# KickerBoard-new.net
KiCad netlist of a schematic drawn in EAGLE
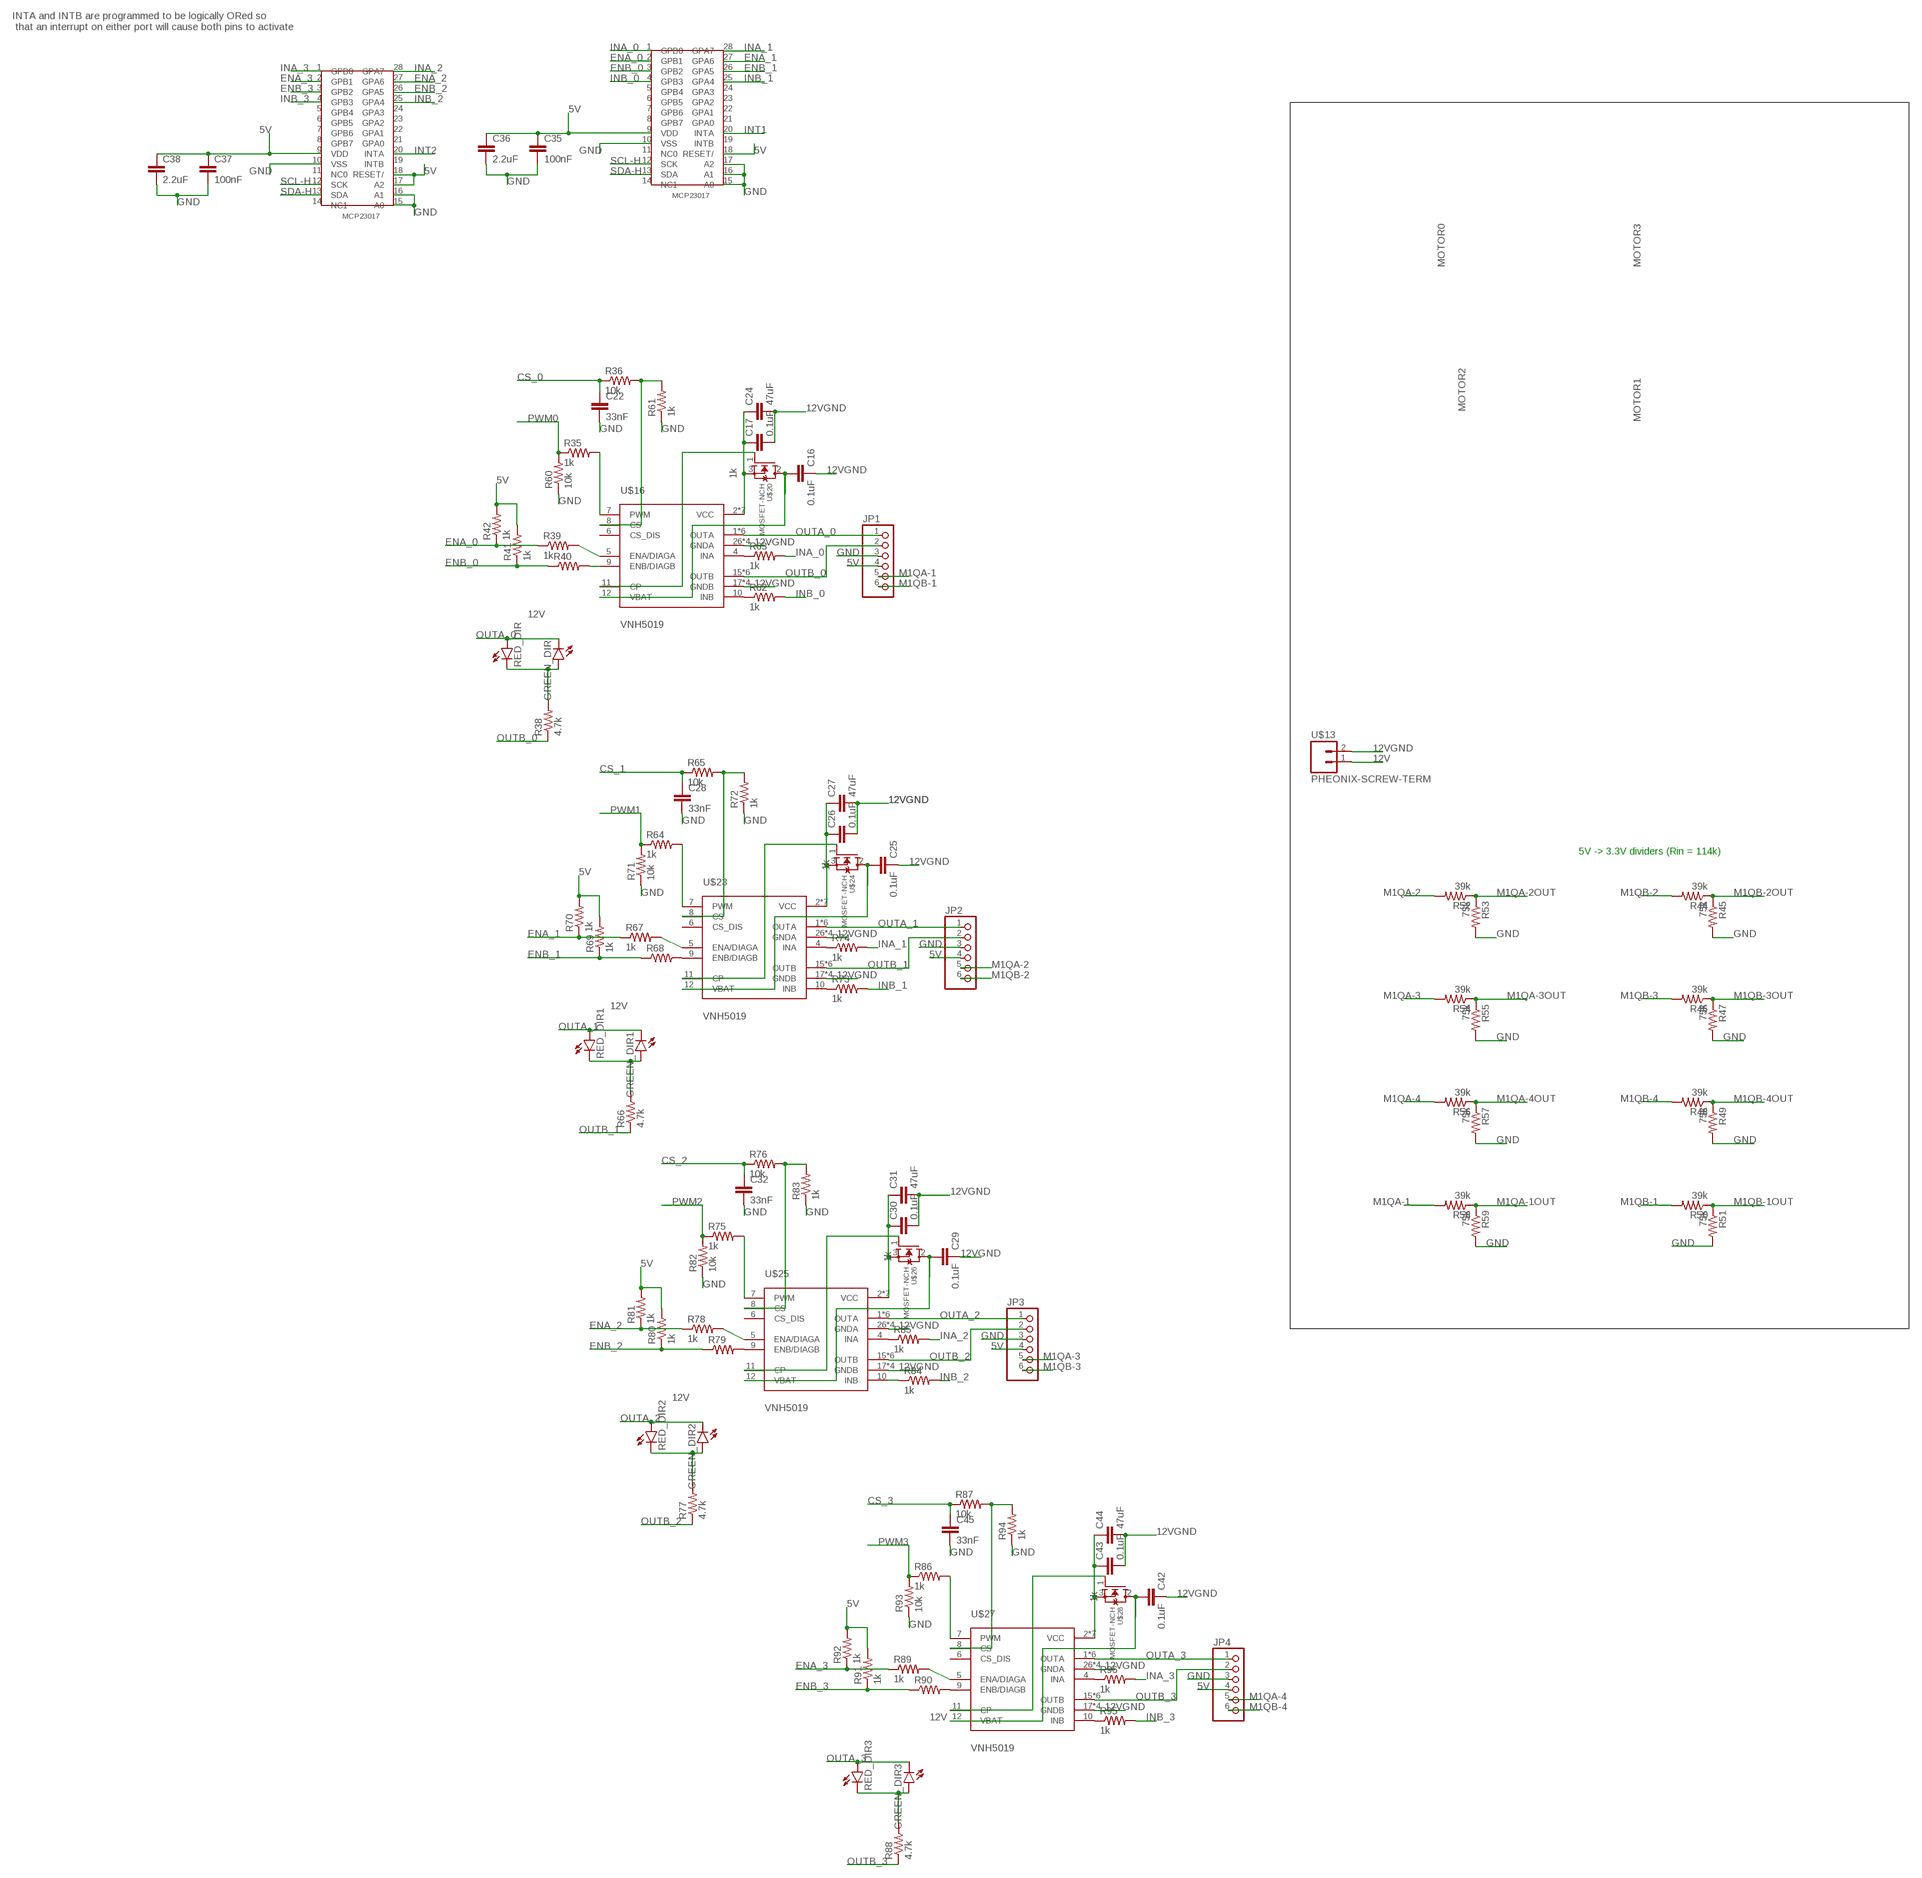
[diagram p0: schematic, sheet 1, part 1 of 3]
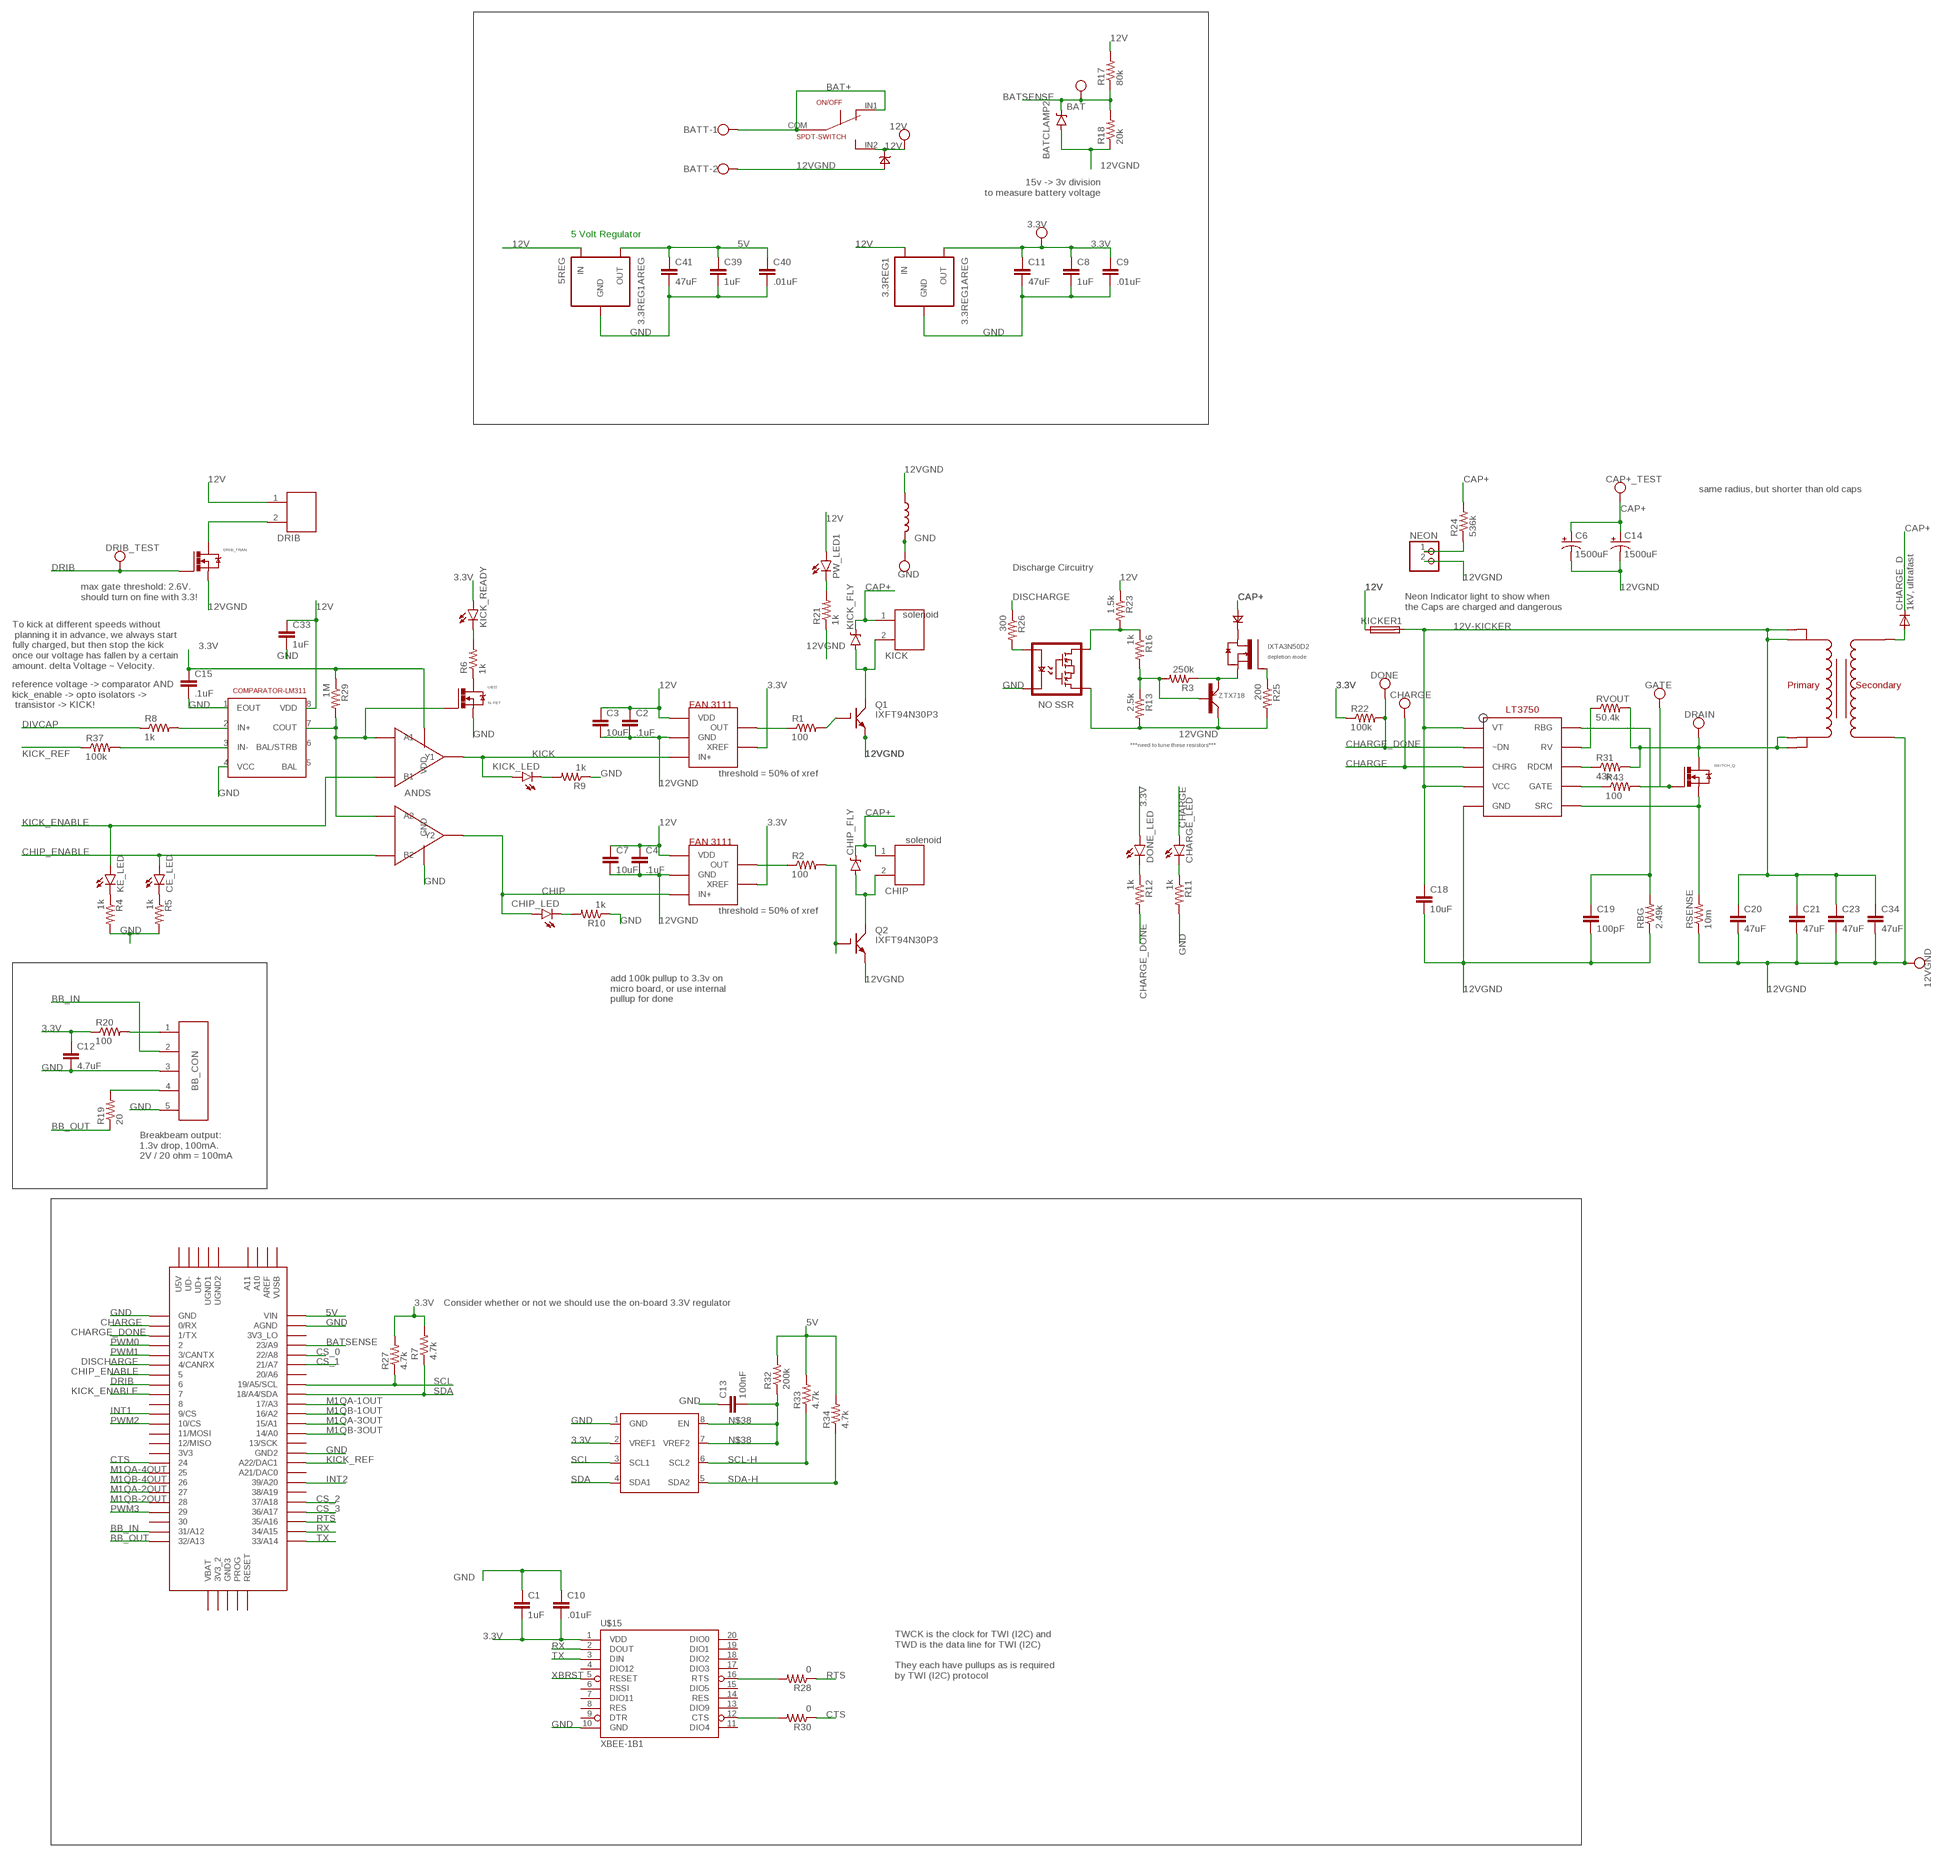
[diagram p1: schematic, sheet 1, part 2 of 3]
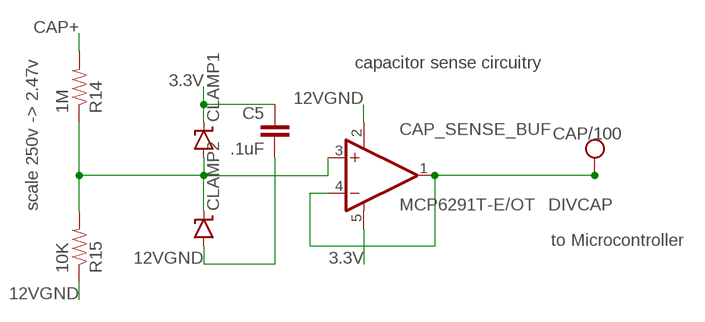
[diagram p2: schematic, sheet 1, part 3 of 3]

(export (version "E")
  (design (tool "Eeschema 10.0.6"))
  (components
    (comp (ref "3.3REG1")
      (value "3.3REG1AREG")
      (footprint "eagle-import:DPAK")
      (libsource (lib "eagle-import") (part "3.3REG1AREG"))
    )
    (comp (ref "3.3V")
      (value "TEST_PT")
      (footprint "eagle-import:TESTING_PT")
      (libsource (lib "eagle-import") (part "TEST_PT"))
    )
    (comp (ref "5REG")
      (value "3.3REG1AREG")
      (footprint "eagle-import:DPAK")
      (libsource (lib "eagle-import") (part "3.3REG1AREG"))
    )
    (comp (ref "12V")
      (value "TEST_PT")
      (footprint "eagle-import:TESTING_PT")
      (libsource (lib "eagle-import") (part "TEST_PT"))
    )
    (comp (ref "12VGND")
      (value "TEST_PT")
      (footprint "eagle-import:TESTING_PT")
      (libsource (lib "eagle-import") (part "TEST_PT"))
    )
    (comp (ref "ANDS")
      (value "AND-DUAL")
      (footprint "eagle-import:TSSOP8")
      (libsource (lib "eagle-import") (part "AND-DUAL"))
    )
    (comp (ref "BAT")
      (value "TEST_PT")
      (footprint "eagle-import:TESTING_PT")
      (libsource (lib "eagle-import") (part "TEST_PT"))
    )
    (comp (ref "BATCLAMP2")
      (value "DIODE-ZENERDO214AC")
      (footprint "eagle-import:DO214AC")
      (libsource (lib "eagle-import") (part "DIODE-ZENERDO214AC"))
    )
    (comp (ref "BATT")
      (value "W237-102")
      (footprint "eagle-import:W237-102")
      (fields (field (name "MPN") "237-102"))
      (libsource (lib "eagle-import") (part "W237-102"))
    )
    (comp (ref "BB_CON")
      (value "JST-5")
      (footprint "eagle-import:JST-5-2MM")
      (libsource (lib "eagle-import") (part "JST-5"))
    )
    (comp (ref "C1")
      (value "1uF")
      (footprint "eagle-import:1206")
      (libsource (lib "eagle-import") (part "CAP1206"))
    )
    (comp (ref "C2")
      (value ".1uF")
      (footprint "eagle-import:1206")
      (libsource (lib "eagle-import") (part "CAP1206"))
    )
    (comp (ref "C3")
      (value "10uF")
      (footprint "eagle-import:1206")
      (libsource (lib "eagle-import") (part "CAP1206"))
    )
    (comp (ref "C4")
      (value ".1uF")
      (footprint "eagle-import:1206")
      (libsource (lib "eagle-import") (part "CAP1206"))
    )
    (comp (ref "C5")
      (value ".1uF")
      (footprint "eagle-import:0805")
      (libsource (lib "eagle-import") (part "CAP0805"))
    )
    (comp (ref "C6")
      (value "1500uF")
      (footprint "eagle-import:EB35D")
      (libsource (lib "eagle-import") (part "CPOL-USE10-35"))
    )
    (comp (ref "C7")
      (value "10uF")
      (footprint "eagle-import:1206")
      (libsource (lib "eagle-import") (part "CAP1206"))
    )
    (comp (ref "C8")
      (value "1uF")
      (footprint "eagle-import:0805")
      (libsource (lib "eagle-import") (part "CAP0805"))
    )
    (comp (ref "C9")
      (value ".01uF")
      (footprint "eagle-import:0805")
      (libsource (lib "eagle-import") (part "CAP0805"))
    )
    (comp (ref "C10")
      (value ".01uF")
      (footprint "eagle-import:1206")
      (libsource (lib "eagle-import") (part "CAP1206"))
    )
    (comp (ref "C11")
      (value "47uF")
      (footprint "eagle-import:1206")
      (libsource (lib "eagle-import") (part "CAP1206"))
    )
    (comp (ref "C12")
      (value "4.7uF")
      (footprint "eagle-import:0805")
      (libsource (lib "eagle-import") (part "CAP0805"))
    )
    (comp (ref "C13")
      (value "100nF")
      (footprint "eagle-import:0805")
      (libsource (lib "eagle-import") (part "CAP0805"))
    )
    (comp (ref "C14")
      (value "1500uF")
      (footprint "eagle-import:EB35D")
      (libsource (lib "eagle-import") (part "CPOL-USE10-35"))
    )
    (comp (ref "C15")
      (value ".1uF")
      (footprint "eagle-import:0805")
      (libsource (lib "eagle-import") (part "CAP0805"))
    )
    (comp (ref "C16")
      (value "0.1uF")
      (footprint "eagle-import:0805")
      (libsource (lib "eagle-import") (part "CAP0805"))
    )
    (comp (ref "C17")
      (value "0.1uF")
      (footprint "eagle-import:0805")
      (libsource (lib "eagle-import") (part "CAP0805"))
    )
    (comp (ref "C18")
      (value "10uF")
      (footprint "eagle-import:0805")
      (libsource (lib "eagle-import") (part "CAP0805"))
    )
    (comp (ref "C19")
      (value "100pF")
      (footprint "eagle-import:0805")
      (libsource (lib "eagle-import") (part "CAP0805"))
    )
    (comp (ref "C20")
      (value "47uF")
      (footprint "eagle-import:1206")
      (libsource (lib "eagle-import") (part "CAP1206"))
    )
    (comp (ref "C21")
      (value "47uF")
      (footprint "eagle-import:1206")
      (libsource (lib "eagle-import") (part "CAP1206"))
    )
    (comp (ref "C22")
      (value "33nF")
      (footprint "eagle-import:0805")
      (libsource (lib "eagle-import") (part "CAP0805"))
    )
    (comp (ref "C23")
      (value "47uF")
      (footprint "eagle-import:1206")
      (libsource (lib "eagle-import") (part "CAP1206"))
    )
    (comp (ref "C24")
      (value "47uF")
      (footprint "eagle-import:1206")
      (libsource (lib "eagle-import") (part "CAP1206"))
    )
    (comp (ref "C25")
      (value "0.1uF")
      (footprint "eagle-import:0805")
      (libsource (lib "eagle-import") (part "CAP0805"))
    )
    (comp (ref "C26")
      (value "0.1uF")
      (footprint "eagle-import:0805")
      (libsource (lib "eagle-import") (part "CAP0805"))
    )
    (comp (ref "C27")
      (value "47uF")
      (footprint "eagle-import:1206")
      (libsource (lib "eagle-import") (part "CAP1206"))
    )
    (comp (ref "C28")
      (value "33nF")
      (footprint "eagle-import:0805")
      (libsource (lib "eagle-import") (part "CAP0805"))
    )
    (comp (ref "C29")
      (value "0.1uF")
      (footprint "eagle-import:0805")
      (libsource (lib "eagle-import") (part "CAP0805"))
    )
    (comp (ref "C30")
      (value "0.1uF")
      (footprint "eagle-import:0805")
      (libsource (lib "eagle-import") (part "CAP0805"))
    )
    (comp (ref "C31")
      (value "47uF")
      (footprint "eagle-import:1206")
      (libsource (lib "eagle-import") (part "CAP1206"))
    )
    (comp (ref "C32")
      (value "33nF")
      (footprint "eagle-import:0805")
      (libsource (lib "eagle-import") (part "CAP0805"))
    )
    (comp (ref "C33")
      (value "1uF")
      (footprint "eagle-import:1206")
      (libsource (lib "eagle-import") (part "CAP1206"))
    )
    (comp (ref "C34")
      (value "47uF")
      (footprint "eagle-import:1206")
      (libsource (lib "eagle-import") (part "CAP1206"))
    )
    (comp (ref "C35")
      (value "100nF")
      (footprint "eagle-import:0805")
      (libsource (lib "eagle-import") (part "CAP0805"))
    )
    (comp (ref "C36")
      (value "2.2uF")
      (footprint "eagle-import:0805")
      (libsource (lib "eagle-import") (part "CAP0805"))
    )
    (comp (ref "C37")
      (value "100nF")
      (footprint "eagle-import:0805")
      (libsource (lib "eagle-import") (part "CAP0805"))
    )
    (comp (ref "C38")
      (value "2.2uF")
      (footprint "eagle-import:0805")
      (libsource (lib "eagle-import") (part "CAP0805"))
    )
    (comp (ref "C39")
      (value "1uF")
      (footprint "eagle-import:0805")
      (libsource (lib "eagle-import") (part "CAP0805"))
    )
    (comp (ref "C40")
      (value ".01uF")
      (footprint "eagle-import:0805")
      (libsource (lib "eagle-import") (part "CAP0805"))
    )
    (comp (ref "C41")
      (value "47uF")
      (footprint "eagle-import:1206")
      (libsource (lib "eagle-import") (part "CAP1206"))
    )
    (comp (ref "C42")
      (value "0.1uF")
      (footprint "eagle-import:0805")
      (libsource (lib "eagle-import") (part "CAP0805"))
    )
    (comp (ref "C43")
      (value "0.1uF")
      (footprint "eagle-import:0805")
      (libsource (lib "eagle-import") (part "CAP0805"))
    )
    (comp (ref "C44")
      (value "47uF")
      (footprint "eagle-import:1206")
      (libsource (lib "eagle-import") (part "CAP1206"))
    )
    (comp (ref "C45")
      (value "33nF")
      (footprint "eagle-import:0805")
      (libsource (lib "eagle-import") (part "CAP0805"))
    )
    (comp (ref "CAP+_TEST")
      (value "TEST_PT")
      (footprint "eagle-import:TESTING_PT")
      (libsource (lib "eagle-import") (part "TEST_PT"))
    )
    (comp (ref "CAP/100")
      (value "TEST_PT")
      (footprint "eagle-import:TESTING_PT")
      (libsource (lib "eagle-import") (part "TEST_PT"))
    )
    (comp (ref "CAP_SENSE_BUF")
      (value "MCP6291T-E/OT")
      (footprint "eagle-import:SOT23-5")
      (libsource (lib "eagle-import") (part "MCP6291T-E/OT"))
    )
    (comp (ref "CE_LED")
      (value "LED1206")
      (footprint "eagle-import:LED-1206")
      (libsource (lib "eagle-import") (part "LED1206"))
    )
    (comp (ref "CHARGE")
      (value "TEST_PT")
      (footprint "eagle-import:TESTING_PT")
      (libsource (lib "eagle-import") (part "TEST_PT"))
    )
    (comp (ref "CHARGE_D")
      (value "1kV, ultrafast")
      (footprint "eagle-import:DO214AC")
      (libsource (lib "eagle-import") (part "DIODE-DO214AC"))
    )
    (comp (ref "CHARGE_LED")
      (value "LED1206")
      (footprint "eagle-import:LED-1206")
      (libsource (lib "eagle-import") (part "LED1206"))
    )
    (comp (ref "CHARGE_U")
      (value "LT3750")
      (footprint "eagle-import:10-MSOP")
      (libsource (lib "eagle-import") (part "LT3750"))
    )
    (comp (ref "CHIP")
      (value "JST-22MM")
      (footprint "eagle-import:JST-2-2MM")
      (libsource (lib "eagle-import") (part "JST-22MM"))
    )
    (comp (ref "CHIP_FLY")
      (value "DIODE-ZENERDO214AB")
      (footprint "eagle-import:DO214AB")
      (libsource (lib "eagle-import") (part "DIODE-ZENERDO214AB"))
    )
    (comp (ref "CHIP_LED")
      (value "LED1206")
      (footprint "eagle-import:LED-1206")
      (libsource (lib "eagle-import") (part "LED1206"))
    )
    (comp (ref "CLAMP1")
      (value "DIODE-ZENERDO214AC")
      (footprint "eagle-import:DO214AC")
      (libsource (lib "eagle-import") (part "DIODE-ZENERDO214AC"))
    )
    (comp (ref "CLAMP2")
      (value "DIODE-ZENERDO214AC")
      (footprint "eagle-import:DO214AC")
      (libsource (lib "eagle-import") (part "DIODE-ZENERDO214AC"))
    )
    (comp (ref "DONE")
      (value "TEST_PT")
      (footprint "eagle-import:TESTING_PT")
      (libsource (lib "eagle-import") (part "TEST_PT"))
    )
    (comp (ref "DONE_LED")
      (value "LED1206")
      (footprint "eagle-import:LED-1206")
      (libsource (lib "eagle-import") (part "LED1206"))
    )
    (comp (ref "DRAIN")
      (value "TEST_PT")
      (footprint "eagle-import:TESTING_PT")
      (libsource (lib "eagle-import") (part "TEST_PT"))
    )
    (comp (ref "DRIB")
      (value "JST-22MM")
      (footprint "eagle-import:JST-2-2MM")
      (libsource (lib "eagle-import") (part "JST-22MM"))
    )
    (comp (ref "DRIB_TEST")
      (value "TEST_PT")
      (footprint "eagle-import:TESTING_PT")
      (libsource (lib "eagle-import") (part "TEST_PT"))
    )
    (comp (ref "DRIB_TRAN")
      (value "N-MOSFETDPAK")
      (footprint "eagle-import:DPAK")
      (libsource (lib "eagle-import") (part "N-MOSFETDPAK"))
    )
    (comp (ref "GATE")
      (value "TEST_PT")
      (footprint "eagle-import:TESTING_PT")
      (libsource (lib "eagle-import") (part "TEST_PT"))
    )
    (comp (ref "GND")
      (value "TEST_PT")
      (footprint "eagle-import:TESTING_PT")
      (libsource (lib "eagle-import") (part "TEST_PT"))
    )
    (comp (ref "GREEN_DIR")
      (value "LED1206")
      (footprint "eagle-import:LED-1206")
      (libsource (lib "eagle-import") (part "LED1206"))
    )
    (comp (ref "GREEN_DIR1")
      (value "LED1206")
      (footprint "eagle-import:LED-1206")
      (libsource (lib "eagle-import") (part "LED1206"))
    )
    (comp (ref "GREEN_DIR2")
      (value "LED1206")
      (footprint "eagle-import:LED-1206")
      (libsource (lib "eagle-import") (part "LED1206"))
    )
    (comp (ref "GREEN_DIR3")
      (value "LED1206")
      (footprint "eagle-import:LED-1206")
      (libsource (lib "eagle-import") (part "LED1206"))
    )
    (comp (ref "JP1")
      (value "PINHD-1X6")
      (footprint "eagle-import:1X06")
      (libsource (lib "eagle-import") (part "PINHD-1X6"))
    )
    (comp (ref "JP2")
      (value "PINHD-1X6")
      (footprint "eagle-import:1X06")
      (libsource (lib "eagle-import") (part "PINHD-1X6"))
    )
    (comp (ref "JP3")
      (value "PINHD-1X6")
      (footprint "eagle-import:1X06")
      (libsource (lib "eagle-import") (part "PINHD-1X6"))
    )
    (comp (ref "JP4")
      (value "PINHD-1X6")
      (footprint "eagle-import:1X06")
      (libsource (lib "eagle-import") (part "PINHD-1X6"))
    )
    (comp (ref "KE_LED")
      (value "LED1206")
      (footprint "eagle-import:LED-1206")
      (libsource (lib "eagle-import") (part "LED1206"))
    )
    (comp (ref "KICK")
      (value "JST-22MM")
      (footprint "eagle-import:JST-2-2MM")
      (libsource (lib "eagle-import") (part "JST-22MM"))
    )
    (comp (ref "KICKER1")
      (value "TR5")
      (footprint "eagle-import:TR5")
      (libsource (lib "eagle-import") (part "TR5"))
    )
    (comp (ref "KICK_FLY")
      (value "DIODE-ZENERDO214AB")
      (footprint "eagle-import:DO214AB")
      (libsource (lib "eagle-import") (part "DIODE-ZENERDO214AB"))
    )
    (comp (ref "KICK_LED")
      (value "LED1206")
      (footprint "eagle-import:LED-1206")
      (libsource (lib "eagle-import") (part "LED1206"))
    )
    (comp (ref "KICK_READY")
      (value "LED1206")
      (footprint "eagle-import:LED-1206")
      (libsource (lib "eagle-import") (part "LED1206"))
    )
    (comp (ref "NEON")
      (value "PINHD-1X2")
      (footprint "eagle-import:1X02")
      (libsource (lib "eagle-import") (part "PINHD-1X2"))
    )
    (comp (ref "ON/OFF")
      (value "SPDT-SWITCH")
      (footprint "eagle-import:CK_SWITCH")
      (libsource (lib "eagle-import") (part "SPDT-SWITCH"))
    )
    (comp (ref "PW_LED1")
      (value "LED1206")
      (footprint "eagle-import:LED-1206")
      (libsource (lib "eagle-import") (part "LED1206"))
    )
    (comp (ref "Q1")
      (value "IXFT94N30P3")
      (footprint "eagle-import:TO268")
      (libsource (lib "eagle-import") (part "IXG?N170T6"))
    )
    (comp (ref "Q2")
      (value "IXFT94N30P3")
      (footprint "eagle-import:TO268")
      (libsource (lib "eagle-import") (part "IXG?N170T6"))
    )
    (comp (ref "R1")
      (value "100")
      (footprint "eagle-import:0805")
      (libsource (lib "eagle-import") (part "SparkFun-Resistors_RESISTOR0805-RES"))
    )
    (comp (ref "R2")
      (value "100")
      (footprint "eagle-import:0805")
      (libsource (lib "eagle-import") (part "SparkFun-Resistors_RESISTOR0805-RES"))
    )
    (comp (ref "R3")
      (value "250k")
      (footprint "eagle-import:0805")
      (libsource (lib "eagle-import") (part "RESISTOR0805-RES"))
    )
    (comp (ref "R4")
      (value "1k")
      (footprint "eagle-import:0805")
      (libsource (lib "eagle-import") (part "RESISTOR0805-RES"))
    )
    (comp (ref "R5")
      (value "1k")
      (footprint "eagle-import:0805")
      (libsource (lib "eagle-import") (part "RESISTOR0805-RES"))
    )
    (comp (ref "R6")
      (value "1k")
      (footprint "eagle-import:0805")
      (libsource (lib "eagle-import") (part "RESISTOR0805-RES"))
    )
    (comp (ref "R7")
      (value "4.7k")
      (footprint "eagle-import:0805")
      (libsource (lib "eagle-import") (part "SparkFun-Resistors_RESISTOR0805-RES"))
    )
    (comp (ref "R8")
      (value "1k")
      (footprint "eagle-import:0805")
      (libsource (lib "eagle-import") (part "RESISTOR0805-RES"))
    )
    (comp (ref "R9")
      (value "1k")
      (footprint "eagle-import:0805")
      (libsource (lib "eagle-import") (part "RESISTOR0805-RES"))
    )
    (comp (ref "R10")
      (value "1k")
      (footprint "eagle-import:0805")
      (libsource (lib "eagle-import") (part "RESISTOR0805-RES"))
    )
    (comp (ref "R11")
      (value "1k")
      (footprint "eagle-import:0805")
      (libsource (lib "eagle-import") (part "RESISTOR0805-RES"))
    )
    (comp (ref "R12")
      (value "1k")
      (footprint "eagle-import:0805")
      (libsource (lib "eagle-import") (part "RESISTOR0805-RES"))
    )
    (comp (ref "R13")
      (value "2.5k")
      (footprint "eagle-import:0805")
      (libsource (lib "eagle-import") (part "RESISTOR0805-RES"))
    )
    (comp (ref "R14")
      (value "1M")
      (footprint "eagle-import:0805")
      (libsource (lib "eagle-import") (part "SparkFun-Resistors_RESISTOR0805-RES"))
    )
    (comp (ref "R15")
      (value "10K")
      (footprint "eagle-import:0805")
      (libsource (lib "eagle-import") (part "SparkFun-Resistors_RESISTOR0805-RES"))
    )
    (comp (ref "R16")
      (value "1k")
      (footprint "eagle-import:0805")
      (libsource (lib "eagle-import") (part "RESISTOR0805-RES"))
    )
    (comp (ref "R17")
      (value "80k")
      (footprint "eagle-import:0805")
      (libsource (lib "eagle-import") (part "RESISTOR0805-RES"))
    )
    (comp (ref "R18")
      (value "20k")
      (footprint "eagle-import:0805")
      (libsource (lib "eagle-import") (part "RESISTOR0805-RES"))
    )
    (comp (ref "R19")
      (value "20")
      (footprint "eagle-import:0805")
      (libsource (lib "eagle-import") (part "RESISTOR0805-RES"))
    )
    (comp (ref "R20")
      (value "100")
      (footprint "eagle-import:0805")
      (libsource (lib "eagle-import") (part "RESISTOR0805-RES"))
    )
    (comp (ref "R21")
      (value "1k")
      (footprint "eagle-import:0805")
      (libsource (lib "eagle-import") (part "RESISTOR0805-RES"))
    )
    (comp (ref "R22")
      (value "100k")
      (footprint "eagle-import:0805")
      (libsource (lib "eagle-import") (part "RESISTOR0805-RES"))
    )
    (comp (ref "R23")
      (value "1.5k")
      (footprint "eagle-import:0805")
      (libsource (lib "eagle-import") (part "RESISTOR0805-RES"))
    )
    (comp (ref "R24")
      (value "536k")
      (footprint "eagle-import:0805")
      (libsource (lib "eagle-import") (part "RESISTOR0805-RES"))
    )
    (comp (ref "R25")
      (value "200")
      (footprint "eagle-import:0805")
      (libsource (lib "eagle-import") (part "RESISTOR0805-RES"))
    )
    (comp (ref "R26")
      (value "300")
      (footprint "eagle-import:0805")
      (libsource (lib "eagle-import") (part "RESISTOR0805-RES"))
    )
    (comp (ref "R27")
      (value "4.7k")
      (footprint "eagle-import:0805")
      (libsource (lib "eagle-import") (part "SparkFun-Resistors_RESISTOR0805-RES"))
    )
    (comp (ref "R28")
      (value "0")
      (footprint "eagle-import:0805")
      (libsource (lib "eagle-import") (part "SparkFun-Resistors_RESISTOR0805-RES"))
    )
    (comp (ref "R29")
      (value "1M")
      (footprint "eagle-import:0805")
      (libsource (lib "eagle-import") (part "RESISTOR0805-RES"))
    )
    (comp (ref "R30")
      (value "0")
      (footprint "eagle-import:0805")
      (libsource (lib "eagle-import") (part "SparkFun-Resistors_RESISTOR0805-RES"))
    )
    (comp (ref "R31")
      (value "43k")
      (footprint "eagle-import:0805")
      (libsource (lib "eagle-import") (part "RESISTOR0805-RES"))
    )
    (comp (ref "R32")
      (value "200k")
      (footprint "eagle-import:0805")
      (libsource (lib "eagle-import") (part "SparkFun-Resistors_RESISTOR0805-RES"))
    )
    (comp (ref "R33")
      (value "4.7k")
      (footprint "eagle-import:0805")
      (libsource (lib "eagle-import") (part "SparkFun-Resistors_RESISTOR0805-RES"))
    )
    (comp (ref "R34")
      (value "4.7k")
      (footprint "eagle-import:0805")
      (libsource (lib "eagle-import") (part "SparkFun-Resistors_RESISTOR0805-RES"))
    )
    (comp (ref "R35")
      (value "1k")
      (footprint "eagle-import:0805")
      (libsource (lib "eagle-import") (part "RESISTOR0805-RES"))
    )
    (comp (ref "R36")
      (value "10k")
      (footprint "eagle-import:0805")
      (libsource (lib "eagle-import") (part "RESISTOR0805-RES"))
    )
    (comp (ref "R37")
      (value "100k")
      (footprint "eagle-import:0805")
      (libsource (lib "eagle-import") (part "RESISTOR0805-RES"))
    )
    (comp (ref "R38")
      (value "4.7k")
      (footprint "eagle-import:0805")
      (libsource (lib "eagle-import") (part "RESISTOR0805-RES"))
    )
    (comp (ref "R39")
      (value "1k")
      (footprint "eagle-import:0805")
      (libsource (lib "eagle-import") (part "RESISTOR0805-RES"))
    )
    (comp (ref "R40")
      (value "1k")
      (footprint "eagle-import:0805")
      (libsource (lib "eagle-import") (part "RESISTOR0805-RES"))
    )
    (comp (ref "R41")
      (value "1k")
      (footprint "eagle-import:0805")
      (libsource (lib "eagle-import") (part "RESISTOR0805-RES"))
    )
    (comp (ref "R42")
      (value "1k")
      (footprint "eagle-import:0805")
      (libsource (lib "eagle-import") (part "RESISTOR0805-RES"))
    )
    (comp (ref "R43")
      (value "100")
      (footprint "eagle-import:0805")
      (libsource (lib "eagle-import") (part "RESISTOR0805-RES"))
    )
    (comp (ref "R44")
      (value "39k")
      (footprint "eagle-import:0805")
      (libsource (lib "eagle-import") (part "RESISTOR0805-RES"))
    )
    (comp (ref "R45")
      (value "75k")
      (footprint "eagle-import:0805")
      (libsource (lib "eagle-import") (part "RESISTOR0805-RES"))
    )
    (comp (ref "R46")
      (value "39k")
      (footprint "eagle-import:0805")
      (libsource (lib "eagle-import") (part "RESISTOR0805-RES"))
    )
    (comp (ref "R47")
      (value "75k")
      (footprint "eagle-import:0805")
      (libsource (lib "eagle-import") (part "RESISTOR0805-RES"))
    )
    (comp (ref "R48")
      (value "39k")
      (footprint "eagle-import:0805")
      (libsource (lib "eagle-import") (part "RESISTOR0805-RES"))
    )
    (comp (ref "R49")
      (value "75k")
      (footprint "eagle-import:0805")
      (libsource (lib "eagle-import") (part "RESISTOR0805-RES"))
    )
    (comp (ref "R50")
      (value "39k")
      (footprint "eagle-import:0805")
      (libsource (lib "eagle-import") (part "RESISTOR0805-RES"))
    )
    (comp (ref "R51")
      (value "75k")
      (footprint "eagle-import:0805")
      (libsource (lib "eagle-import") (part "RESISTOR0805-RES"))
    )
    (comp (ref "R52")
      (value "39k")
      (footprint "eagle-import:0805")
      (libsource (lib "eagle-import") (part "RESISTOR0805-RES"))
    )
    (comp (ref "R53")
      (value "75k")
      (footprint "eagle-import:0805")
      (libsource (lib "eagle-import") (part "RESISTOR0805-RES"))
    )
    (comp (ref "R54")
      (value "39k")
      (footprint "eagle-import:0805")
      (libsource (lib "eagle-import") (part "RESISTOR0805-RES"))
    )
    (comp (ref "R55")
      (value "75k")
      (footprint "eagle-import:0805")
      (libsource (lib "eagle-import") (part "RESISTOR0805-RES"))
    )
    (comp (ref "R56")
      (value "39k")
      (footprint "eagle-import:0805")
      (libsource (lib "eagle-import") (part "RESISTOR0805-RES"))
    )
    (comp (ref "R57")
      (value "75k")
      (footprint "eagle-import:0805")
      (libsource (lib "eagle-import") (part "RESISTOR0805-RES"))
    )
    (comp (ref "R58")
      (value "39k")
      (footprint "eagle-import:0805")
      (libsource (lib "eagle-import") (part "RESISTOR0805-RES"))
    )
    (comp (ref "R59")
      (value "75k")
      (footprint "eagle-import:0805")
      (libsource (lib "eagle-import") (part "RESISTOR0805-RES"))
    )
    (comp (ref "R60")
      (value "10k")
      (footprint "eagle-import:0805")
      (libsource (lib "eagle-import") (part "RESISTOR0805-RES"))
    )
    (comp (ref "R61")
      (value "1k")
      (footprint "eagle-import:0805")
      (libsource (lib "eagle-import") (part "RESISTOR0805-RES"))
    )
    (comp (ref "R62")
      (value "1k")
      (footprint "eagle-import:0805")
      (libsource (lib "eagle-import") (part "RESISTOR0805-RES"))
    )
    (comp (ref "R63")
      (value "1k")
      (footprint "eagle-import:0805")
      (libsource (lib "eagle-import") (part "RESISTOR0805-RES"))
    )
    (comp (ref "R64")
      (value "1k")
      (footprint "eagle-import:0805")
      (libsource (lib "eagle-import") (part "RESISTOR0805-RES"))
    )
    (comp (ref "R65")
      (value "10k")
      (footprint "eagle-import:0805")
      (libsource (lib "eagle-import") (part "RESISTOR0805-RES"))
    )
    (comp (ref "R66")
      (value "4.7k")
      (footprint "eagle-import:0805")
      (libsource (lib "eagle-import") (part "RESISTOR0805-RES"))
    )
    (comp (ref "R67")
      (value "1k")
      (footprint "eagle-import:0805")
      (libsource (lib "eagle-import") (part "RESISTOR0805-RES"))
    )
    (comp (ref "R68")
      (value "1k")
      (footprint "eagle-import:0805")
      (libsource (lib "eagle-import") (part "RESISTOR0805-RES"))
    )
    (comp (ref "R69")
      (value "1k")
      (footprint "eagle-import:0805")
      (libsource (lib "eagle-import") (part "RESISTOR0805-RES"))
    )
    (comp (ref "R70")
      (value "1k")
      (footprint "eagle-import:0805")
      (libsource (lib "eagle-import") (part "RESISTOR0805-RES"))
    )
    (comp (ref "R71")
      (value "10k")
      (footprint "eagle-import:0805")
      (libsource (lib "eagle-import") (part "RESISTOR0805-RES"))
    )
    (comp (ref "R72")
      (value "1k")
      (footprint "eagle-import:0805")
      (libsource (lib "eagle-import") (part "RESISTOR0805-RES"))
    )
    (comp (ref "R73")
      (value "1k")
      (footprint "eagle-import:0805")
      (libsource (lib "eagle-import") (part "RESISTOR0805-RES"))
    )
    (comp (ref "R74")
      (value "1k")
      (footprint "eagle-import:0805")
      (libsource (lib "eagle-import") (part "RESISTOR0805-RES"))
    )
    (comp (ref "R75")
      (value "1k")
      (footprint "eagle-import:0805")
      (libsource (lib "eagle-import") (part "RESISTOR0805-RES"))
    )
    (comp (ref "R76")
      (value "10k")
      (footprint "eagle-import:0805")
      (libsource (lib "eagle-import") (part "RESISTOR0805-RES"))
    )
    (comp (ref "R77")
      (value "4.7k")
      (footprint "eagle-import:0805")
      (libsource (lib "eagle-import") (part "RESISTOR0805-RES"))
    )
    (comp (ref "R78")
      (value "1k")
      (footprint "eagle-import:0805")
      (libsource (lib "eagle-import") (part "RESISTOR0805-RES"))
    )
    (comp (ref "R79")
      (value "1k")
      (footprint "eagle-import:0805")
      (libsource (lib "eagle-import") (part "RESISTOR0805-RES"))
    )
    (comp (ref "R80")
      (value "1k")
      (footprint "eagle-import:0805")
      (libsource (lib "eagle-import") (part "RESISTOR0805-RES"))
    )
    (comp (ref "R81")
      (value "1k")
      (footprint "eagle-import:0805")
      (libsource (lib "eagle-import") (part "RESISTOR0805-RES"))
    )
    (comp (ref "R82")
      (value "10k")
      (footprint "eagle-import:0805")
      (libsource (lib "eagle-import") (part "RESISTOR0805-RES"))
    )
    (comp (ref "R83")
      (value "1k")
      (footprint "eagle-import:0805")
      (libsource (lib "eagle-import") (part "RESISTOR0805-RES"))
    )
    (comp (ref "R84")
      (value "1k")
      (footprint "eagle-import:0805")
      (libsource (lib "eagle-import") (part "RESISTOR0805-RES"))
    )
    (comp (ref "R85")
      (value "1k")
      (footprint "eagle-import:0805")
      (libsource (lib "eagle-import") (part "RESISTOR0805-RES"))
    )
    (comp (ref "R86")
      (value "1k")
      (footprint "eagle-import:0805")
      (libsource (lib "eagle-import") (part "RESISTOR0805-RES"))
    )
    (comp (ref "R87")
      (value "10k")
      (footprint "eagle-import:0805")
      (libsource (lib "eagle-import") (part "RESISTOR0805-RES"))
    )
    (comp (ref "R88")
      (value "4.7k")
      (footprint "eagle-import:0805")
      (libsource (lib "eagle-import") (part "RESISTOR0805-RES"))
    )
    (comp (ref "R89")
      (value "1k")
      (footprint "eagle-import:0805")
      (libsource (lib "eagle-import") (part "RESISTOR0805-RES"))
    )
    (comp (ref "R90")
      (value "1k")
      (footprint "eagle-import:0805")
      (libsource (lib "eagle-import") (part "RESISTOR0805-RES"))
    )
    (comp (ref "R91")
      (value "1k")
      (footprint "eagle-import:0805")
      (libsource (lib "eagle-import") (part "RESISTOR0805-RES"))
    )
    (comp (ref "R92")
      (value "1k")
      (footprint "eagle-import:0805")
      (libsource (lib "eagle-import") (part "RESISTOR0805-RES"))
    )
    (comp (ref "R93")
      (value "10k")
      (footprint "eagle-import:0805")
      (libsource (lib "eagle-import") (part "RESISTOR0805-RES"))
    )
    (comp (ref "R94")
      (value "1k")
      (footprint "eagle-import:0805")
      (libsource (lib "eagle-import") (part "RESISTOR0805-RES"))
    )
    (comp (ref "R95")
      (value "1k")
      (footprint "eagle-import:0805")
      (libsource (lib "eagle-import") (part "RESISTOR0805-RES"))
    )
    (comp (ref "R96")
      (value "1k")
      (footprint "eagle-import:0805")
      (libsource (lib "eagle-import") (part "RESISTOR0805-RES"))
    )
    (comp (ref "RBG")
      (value "2.49k")
      (footprint "eagle-import:0805")
      (libsource (lib "eagle-import") (part "RESISTOR0805-RES"))
    )
    (comp (ref "RED_DIR")
      (value "LED1206")
      (footprint "eagle-import:LED-1206")
      (libsource (lib "eagle-import") (part "LED1206"))
    )
    (comp (ref "RED_DIR1")
      (value "LED1206")
      (footprint "eagle-import:LED-1206")
      (libsource (lib "eagle-import") (part "LED1206"))
    )
    (comp (ref "RED_DIR2")
      (value "LED1206")
      (footprint "eagle-import:LED-1206")
      (libsource (lib "eagle-import") (part "LED1206"))
    )
    (comp (ref "RED_DIR3")
      (value "LED1206")
      (footprint "eagle-import:LED-1206")
      (libsource (lib "eagle-import") (part "LED1206"))
    )
    (comp (ref "RSENSE")
      (value "10m")
      (footprint "eagle-import:R2512")
      (libsource (lib "eagle-import") (part "RESISTOR2512"))
    )
    (comp (ref "RVOUT")
      (value "50.4k")
      (footprint "eagle-import:0805")
      (libsource (lib "eagle-import") (part "RESISTOR0805-RES"))
    )
    (comp (ref "SWITCH_Q")
      (value "N-MOSFETDPAK")
      (footprint "eagle-import:DPAK")
      (libsource (lib "eagle-import") (part "N-MOSFETDPAK"))
    )
    (comp (ref "U$1")
      (value "FAN31111")
      (footprint "eagle-import:SOT23-5")
      (libsource (lib "eagle-import") (part "FAN31111"))
    )
    (comp (ref "U$2")
      (value "IXTA3N50D2")
      (footprint "eagle-import:TO-263")
      (libsource (lib "eagle-import") (part "IXTA3N50D2"))
    )
    (comp (ref "U$3")
      (value "32052-TRANSFORMER")
      (footprint "eagle-import:10-TRANSFORMER")
      (libsource (lib "eagle-import") (part "32052-TRANSFORMER"))
    )
    (comp (ref "U$4")
      (value "FAN31111")
      (footprint "eagle-import:SOT23-5")
      (libsource (lib "eagle-import") (part "FAN31111"))
    )
    (comp (ref "U$5")
      (value "VO1400AEFTR")
      (footprint "eagle-import:SOP4")
      (libsource (lib "eagle-import") (part "VO1400AEFTR"))
    )
    (comp (ref "U$6")
      (value "ZTX718")
      (footprint "eagle-import:TO92")
      (libsource (lib "eagle-import") (part "ZTX718"))
    )
    (comp (ref "U$7")
      (value "1N4007")
      (footprint "eagle-import:THROUGH-HOLE-2")
      (libsource (lib "eagle-import") (part "1N4007"))
    )
    (comp (ref "U$8")
      (value "PCA9306")
      (footprint "eagle-import:SOIC8")
      (libsource (lib "eagle-import") (part "PCA9306"))
    )
    (comp (ref "U$12")
      (value "13VZENER")
      (footprint "eagle-import:THROUGH-HOLE-2")
      (libsource (lib "eagle-import") (part "13VZENER"))
    )
    (comp (ref "U$13")
      (value "PHEONIX-SCREW-TERM")
      (footprint "eagle-import:1X02-PHEONIX")
      (libsource (lib "eagle-import") (part "PHEONIX-SCREW-TERM"))
    )
    (comp (ref "U$14")
      (value "TEENSY_3.5/3.6")
      (footprint "eagle-import:TEENSY_3.5_3.6")
      (libsource (lib "eagle-import") (part "TEENSY_3.5/3.6"))
    )
    (comp (ref "U$15")
      (value "XBEE-1B1")
      (footprint "eagle-import:XBEE-1")
      (libsource (lib "eagle-import") (part "XBEE-1B1"))
    )
    (comp (ref "U$16")
      (value "VNH5019")
      (footprint "eagle-import:MULTIPOWERSO-30")
      (libsource (lib "eagle-import") (part "VNH5019"))
    )
    (comp (ref "U$17")
      (value "IO-EXPANDER")
      (footprint "eagle-import:SSOP")
      (libsource (lib "eagle-import") (part "IO-EXPANDER"))
    )
    (comp (ref "U$18")
      (value "LM311")
      (footprint "eagle-import:SOIC8")
      (libsource (lib "eagle-import") (part "LM311"))
    )
    (comp (ref "U$19")
      (value "INDUCTOR")
      (footprint "eagle-import:0805")
      (libsource (lib "eagle-import") (part "INDUCTOR"))
    )
    (comp (ref "U$20")
      (value "MOSFET-NCH")
      (footprint "eagle-import:TO252-3")
      (libsource (lib "eagle-import") (part "MOSFET-NCH"))
    )
    (comp (ref "U$21")
      (value "IO-EXPANDER")
      (footprint "eagle-import:SSOP")
      (libsource (lib "eagle-import") (part "IO-EXPANDER"))
    )
    (comp (ref "U$22")
      (value "N-FET")
      (footprint "eagle-import:SOT-23")
      (libsource (lib "eagle-import") (part "N-FET"))
    )
    (comp (ref "U$23")
      (value "VNH5019")
      (footprint "eagle-import:MULTIPOWERSO-30")
      (libsource (lib "eagle-import") (part "VNH5019"))
    )
    (comp (ref "U$24")
      (value "MOSFET-NCH")
      (footprint "eagle-import:TO252-3")
      (libsource (lib "eagle-import") (part "MOSFET-NCH"))
    )
    (comp (ref "U$25")
      (value "VNH5019")
      (footprint "eagle-import:MULTIPOWERSO-30")
      (libsource (lib "eagle-import") (part "VNH5019"))
    )
    (comp (ref "U$26")
      (value "MOSFET-NCH")
      (footprint "eagle-import:TO252-3")
      (libsource (lib "eagle-import") (part "MOSFET-NCH"))
    )
    (comp (ref "U$27")
      (value "VNH5019")
      (footprint "eagle-import:MULTIPOWERSO-30")
      (libsource (lib "eagle-import") (part "VNH5019"))
    )
    (comp (ref "U$28")
      (value "MOSFET-NCH")
      (footprint "eagle-import:TO252-3")
      (libsource (lib "eagle-import") (part "MOSFET-NCH"))
    )
  )
  (nets
    (net (code "1") (name "/3.3V") (class "Default")
      (node (ref "3.3REG1") (pin "SOURCE") (pinfunction "OUT_SOURCE") (pintype "bidirectional"))
      (node (ref "3.3V") (pin "P$1") (pinfunction "P$1_P$1") (pintype "bidirectional"))
      (node (ref "ANDS") (pin "P$8") (pinfunction "VDD_P$8") (pintype "bidirectional"))
      (node (ref "C1") (pin "2") (pinfunction "2_2") (pintype "passive"))
      (node (ref "C10") (pin "2") (pinfunction "2_2") (pintype "passive"))
      (node (ref "C11") (pin "1") (pinfunction "1_1") (pintype "passive"))
      (node (ref "C12") (pin "1") (pinfunction "1_1") (pintype "passive"))
      (node (ref "C15") (pin "1") (pinfunction "1_1") (pintype "passive"))
      (node (ref "C5") (pin "1") (pinfunction "1_1") (pintype "passive"))
      (node (ref "C8") (pin "1") (pinfunction "1_1") (pintype "passive"))
      (node (ref "C9") (pin "1") (pinfunction "1_1") (pintype "passive"))
      (node (ref "CAP_SENSE_BUF") (pin "5") (pinfunction "V+_5") (pintype "power_in"))
      (node (ref "CLAMP1") (pin "C") (pinfunction "C_C") (pintype "passive"))
      (node (ref "DONE_LED") (pin "A") (pinfunction "A_A") (pintype "passive"))
      (node (ref "KICK_READY") (pin "A") (pinfunction "A_A") (pintype "passive"))
      (node (ref "R20") (pin "1") (pinfunction "1_1") (pintype "passive"))
      (node (ref "R22") (pin "1") (pinfunction "1_1") (pintype "passive"))
      (node (ref "R27") (pin "2") (pinfunction "2_2") (pintype "passive"))
      (node (ref "R29") (pin "1") (pinfunction "1_1") (pintype "passive"))
      (node (ref "R7") (pin "2") (pinfunction "2_2") (pintype "passive"))
      (node (ref "U$1") (pin "4") (pinfunction "XREF_4") (pintype "input"))
      (node (ref "U$15") (pin "1") (pinfunction "VDD_1") (pintype "power_in"))
      (node (ref "U$4") (pin "4") (pinfunction "XREF_4") (pintype "input"))
      (node (ref "U$8") (pin "2") (pinfunction "VREF1_2") (pintype "bidirectional"))
    )
    (net (code "2") (name "/5V") (class "Default")
      (node (ref "5REG") (pin "SOURCE") (pinfunction "OUT_SOURCE") (pintype "bidirectional"))
      (node (ref "C35") (pin "1") (pinfunction "1_1") (pintype "passive"))
      (node (ref "C36") (pin "1") (pinfunction "1_1") (pintype "passive"))
      (node (ref "C37") (pin "1") (pinfunction "1_1") (pintype "passive"))
      (node (ref "C38") (pin "1") (pinfunction "1_1") (pintype "passive"))
      (node (ref "C39") (pin "1") (pinfunction "1_1") (pintype "passive"))
      (node (ref "C40") (pin "1") (pinfunction "1_1") (pintype "passive"))
      (node (ref "C41") (pin "1") (pinfunction "1_1") (pintype "passive"))
      (node (ref "JP1") (pin "4") (pinfunction "4_4") (pintype "passive"))
      (node (ref "JP2") (pin "4") (pinfunction "4_4") (pintype "passive"))
      (node (ref "JP3") (pin "4") (pinfunction "4_4") (pintype "passive"))
      (node (ref "JP4") (pin "4") (pinfunction "4_4") (pintype "passive"))
      (node (ref "R32") (pin "2") (pinfunction "2_2") (pintype "passive"))
      (node (ref "R33") (pin "2") (pinfunction "2_2") (pintype "passive"))
      (node (ref "R34") (pin "2") (pinfunction "2_2") (pintype "passive"))
      (node (ref "R41") (pin "2") (pinfunction "2_2") (pintype "passive"))
      (node (ref "R42") (pin "2") (pinfunction "2_2") (pintype "passive"))
      (node (ref "R69") (pin "2") (pinfunction "2_2") (pintype "passive"))
      (node (ref "R70") (pin "2") (pinfunction "2_2") (pintype "passive"))
      (node (ref "R80") (pin "2") (pinfunction "2_2") (pintype "passive"))
      (node (ref "R81") (pin "2") (pinfunction "2_2") (pintype "passive"))
      (node (ref "R91") (pin "2") (pinfunction "2_2") (pintype "passive"))
      (node (ref "R92") (pin "2") (pinfunction "2_2") (pintype "passive"))
      (node (ref "U$14") (pin "VIN") (pinfunction "VIN_VIN") (pintype "bidirectional"))
      (node (ref "U$17") (pin "18") (pinfunction "RESET/_18") (pintype "bidirectional"))
      (node (ref "U$17") (pin "9") (pinfunction "VDD_9") (pintype "bidirectional"))
      (node (ref "U$21") (pin "17") (pinfunction "A2_17") (pintype "bidirectional"))
      (node (ref "U$21") (pin "18") (pinfunction "RESET/_18") (pintype "bidirectional"))
      (node (ref "U$21") (pin "9") (pinfunction "VDD_9") (pintype "bidirectional"))
    )
    (net (code "3") (name "/12V") (class "Default")
      (node (ref "12V") (pin "P$1") (pinfunction "P$1_P$1") (pintype "bidirectional"))
      (node (ref "3.3REG1") (pin "GATE") (pinfunction "IN_GATE") (pintype "input"))
      (node (ref "5REG") (pin "GATE") (pinfunction "IN_GATE") (pintype "input"))
      (node (ref "C16") (pin "1") (pinfunction "1_1") (pintype "passive"))
      (node (ref "C2") (pin "1") (pinfunction "1_1") (pintype "passive"))
      (node (ref "C25") (pin "1") (pinfunction "1_1") (pintype "passive"))
      (node (ref "C29") (pin "1") (pinfunction "1_1") (pintype "passive"))
      (node (ref "C3") (pin "1") (pinfunction "1_1") (pintype "passive"))
      (node (ref "C33") (pin "1") (pinfunction "1_1") (pintype "passive"))
      (node (ref "C4") (pin "1") (pinfunction "1_1") (pintype "passive"))
      (node (ref "C42") (pin "1") (pinfunction "1_1") (pintype "passive"))
      (node (ref "C7") (pin "1") (pinfunction "1_1") (pintype "passive"))
      (node (ref "DRIB") (pin "1") (pinfunction "P$1_1") (pintype "bidirectional"))
      (node (ref "KICKER1") (pin "1") (pinfunction "1_1") (pintype "passive"))
      (node (ref "ON/OFF") (pin "IN2") (pinfunction "P2_IN2") (pintype "bidirectional"))
      (node (ref "PW_LED1") (pin "A") (pinfunction "A_A") (pintype "passive"))
      (node (ref "R17") (pin "2") (pinfunction "2_2") (pintype "passive"))
      (node (ref "R23") (pin "1") (pinfunction "1_1") (pintype "passive"))
      (node (ref "U$1") (pin "1") (pinfunction "VDD_1") (pintype "power_in"))
      (node (ref "U$12") (pin "-") (pinfunction "-_-") (pintype "bidirectional"))
      (node (ref "U$13") (pin "1") (pinfunction "1_1") (pintype "passive"))
      (node (ref "U$16") (pin "12") (pinfunction "VBAT_12") (pintype "bidirectional"))
      (node (ref "U$18") (pin "8") (pinfunction "VDD_8") (pintype "bidirectional"))
      (node (ref "U$20") (pin "2") (pinfunction "D_2") (pintype "bidirectional"))
      (node (ref "U$23") (pin "12") (pinfunction "VBAT_12") (pintype "bidirectional"))
      (node (ref "U$24") (pin "2") (pinfunction "D_2") (pintype "bidirectional"))
      (node (ref "U$25") (pin "12") (pinfunction "VBAT_12") (pintype "bidirectional"))
      (node (ref "U$26") (pin "2") (pinfunction "D_2") (pintype "bidirectional"))
      (node (ref "U$27") (pin "12") (pinfunction "VBAT_12") (pintype "bidirectional"))
      (node (ref "U$28") (pin "2") (pinfunction "D_2") (pintype "bidirectional"))
      (node (ref "U$4") (pin "1") (pinfunction "VDD_1") (pintype "power_in"))
    )
    (net (code "4") (name "/12V-KICKER") (class "Default")
      (node (ref "C18") (pin "1") (pinfunction "1_1") (pintype "passive"))
      (node (ref "C20") (pin "1") (pinfunction "1_1") (pintype "passive"))
      (node (ref "C21") (pin "1") (pinfunction "1_1") (pintype "passive"))
      (node (ref "C23") (pin "1") (pinfunction "1_1") (pintype "passive"))
      (node (ref "C34") (pin "1") (pinfunction "1_1") (pintype "passive"))
      (node (ref "CHARGE_U") (pin "P$1") (pinfunction "VT_P$1") (pintype "bidirectional"))
      (node (ref "CHARGE_U") (pin "P$4") (pinfunction "VCC_P$4") (pintype "bidirectional"))
      (node (ref "KICKER1") (pin "2") (pinfunction "2_2") (pintype "passive"))
      (node (ref "U$3") (pin "P$4") (pinfunction "P$4_P$4") (pintype "bidirectional"))
      (node (ref "U$3") (pin "P$5") (pinfunction "P$5_P$5") (pintype "bidirectional"))
    )
    (net (code "5") (name "/12VGND") (class "Default")
      (node (ref "12VGND") (pin "P$1") (pinfunction "P$1_P$1") (pintype "bidirectional"))
      (node (ref "BATCLAMP2") (pin "A") (pinfunction "A_A") (pintype "passive"))
      (node (ref "BATT") (pin "2") (pinfunction "KL_2") (pintype "passive"))
      (node (ref "C14") (pin "-") (pinfunction "-_-") (pintype "passive"))
      (node (ref "C16") (pin "2") (pinfunction "2_2") (pintype "passive"))
      (node (ref "C17") (pin "2") (pinfunction "2_2") (pintype "passive"))
      (node (ref "C18") (pin "2") (pinfunction "2_2") (pintype "passive"))
      (node (ref "C19") (pin "2") (pinfunction "2_2") (pintype "passive"))
      (node (ref "C2") (pin "2") (pinfunction "2_2") (pintype "passive"))
      (node (ref "C20") (pin "2") (pinfunction "2_2") (pintype "passive"))
      (node (ref "C21") (pin "2") (pinfunction "2_2") (pintype "passive"))
      (node (ref "C23") (pin "2") (pinfunction "2_2") (pintype "passive"))
      (node (ref "C24") (pin "2") (pinfunction "2_2") (pintype "passive"))
      (node (ref "C25") (pin "2") (pinfunction "2_2") (pintype "passive"))
      (node (ref "C26") (pin "2") (pinfunction "2_2") (pintype "passive"))
      (node (ref "C27") (pin "2") (pinfunction "2_2") (pintype "passive"))
      (node (ref "C29") (pin "2") (pinfunction "2_2") (pintype "passive"))
      (node (ref "C3") (pin "2") (pinfunction "2_2") (pintype "passive"))
      (node (ref "C30") (pin "2") (pinfunction "2_2") (pintype "passive"))
      (node (ref "C31") (pin "2") (pinfunction "2_2") (pintype "passive"))
      (node (ref "C34") (pin "2") (pinfunction "2_2") (pintype "passive"))
      (node (ref "C4") (pin "2") (pinfunction "2_2") (pintype "passive"))
      (node (ref "C42") (pin "2") (pinfunction "2_2") (pintype "passive"))
      (node (ref "C43") (pin "2") (pinfunction "2_2") (pintype "passive"))
      (node (ref "C44") (pin "2") (pinfunction "2_2") (pintype "passive"))
      (node (ref "C5") (pin "2") (pinfunction "2_2") (pintype "passive"))
      (node (ref "C6") (pin "-") (pinfunction "-_-") (pintype "passive"))
      (node (ref "C7") (pin "2") (pinfunction "2_2") (pintype "passive"))
      (node (ref "CAP_SENSE_BUF") (pin "2") (pinfunction "V-_2") (pintype "power_in"))
      (node (ref "CHARGE_U") (pin "P$5") (pinfunction "GND_P$5") (pintype "bidirectional"))
      (node (ref "CLAMP2") (pin "A") (pinfunction "A_A") (pintype "passive"))
      (node (ref "DRIB_TRAN") (pin "SOURCE") (pinfunction "S_SOURCE") (pintype "bidirectional"))
      (node (ref "NEON") (pin "2") (pinfunction "2_2") (pintype "passive"))
      (node (ref "Q1") (pin "E") (pinfunction "E_E") (pintype "passive"))
      (node (ref "Q2") (pin "E") (pinfunction "E_E") (pintype "passive"))
      (node (ref "R13") (pin "2") (pinfunction "2_2") (pintype "passive"))
      (node (ref "R15") (pin "1") (pinfunction "1_1") (pintype "passive"))
      (node (ref "R18") (pin "1") (pinfunction "1_1") (pintype "passive"))
      (node (ref "R21") (pin "1") (pinfunction "1_1") (pintype "passive"))
      (node (ref "R25") (pin "2") (pinfunction "2_2") (pintype "passive"))
      (node (ref "RBG") (pin "1") (pinfunction "1_1") (pintype "passive"))
      (node (ref "RSENSE") (pin "1") (pinfunction "1_1") (pintype "passive"))
      (node (ref "U$1") (pin "2") (pinfunction "GND_2") (pintype "power_in"))
      (node (ref "U$12") (pin "+") (pinfunction "+_+") (pintype "bidirectional"))
      (node (ref "U$13") (pin "2") (pinfunction "2_2") (pintype "passive"))
      (node (ref "U$16") (pin "17") (pinfunction "GNDB_17") (pintype "bidirectional"))
      (node (ref "U$16") (pin "18") (pinfunction "GNDB_18") (pintype "bidirectional"))
      (node (ref "U$16") (pin "19") (pinfunction "GNDB_19") (pintype "bidirectional"))
      (node (ref "U$16") (pin "20") (pinfunction "GNDB_20") (pintype "bidirectional"))
      (node (ref "U$16") (pin "26") (pinfunction "GNDA_26") (pintype "bidirectional"))
      (node (ref "U$16") (pin "27") (pinfunction "GNDA_27") (pintype "bidirectional"))
      (node (ref "U$16") (pin "28") (pinfunction "GNDA_28") (pintype "bidirectional"))
      (node (ref "U$16") (pin "29") (pinfunction "GNDA_29") (pintype "bidirectional"))
      (node (ref "U$19") (pin "1") (pinfunction "P$1_1") (pintype "bidirectional"))
      (node (ref "U$23") (pin "17") (pinfunction "GNDB_17") (pintype "bidirectional"))
      (node (ref "U$23") (pin "18") (pinfunction "GNDB_18") (pintype "bidirectional"))
      (node (ref "U$23") (pin "19") (pinfunction "GNDB_19") (pintype "bidirectional"))
      (node (ref "U$23") (pin "20") (pinfunction "GNDB_20") (pintype "bidirectional"))
      (node (ref "U$23") (pin "26") (pinfunction "GNDA_26") (pintype "bidirectional"))
      (node (ref "U$23") (pin "27") (pinfunction "GNDA_27") (pintype "bidirectional"))
      (node (ref "U$23") (pin "28") (pinfunction "GNDA_28") (pintype "bidirectional"))
      (node (ref "U$23") (pin "29") (pinfunction "GNDA_29") (pintype "bidirectional"))
      (node (ref "U$25") (pin "17") (pinfunction "GNDB_17") (pintype "bidirectional"))
      (node (ref "U$25") (pin "18") (pinfunction "GNDB_18") (pintype "bidirectional"))
      (node (ref "U$25") (pin "19") (pinfunction "GNDB_19") (pintype "bidirectional"))
      (node (ref "U$25") (pin "20") (pinfunction "GNDB_20") (pintype "bidirectional"))
      (node (ref "U$25") (pin "26") (pinfunction "GNDA_26") (pintype "bidirectional"))
      (node (ref "U$25") (pin "27") (pinfunction "GNDA_27") (pintype "bidirectional"))
      (node (ref "U$25") (pin "28") (pinfunction "GNDA_28") (pintype "bidirectional"))
      (node (ref "U$25") (pin "29") (pinfunction "GNDA_29") (pintype "bidirectional"))
      (node (ref "U$27") (pin "17") (pinfunction "GNDB_17") (pintype "bidirectional"))
      (node (ref "U$27") (pin "18") (pinfunction "GNDB_18") (pintype "bidirectional"))
      (node (ref "U$27") (pin "19") (pinfunction "GNDB_19") (pintype "bidirectional"))
      (node (ref "U$27") (pin "20") (pinfunction "GNDB_20") (pintype "bidirectional"))
      (node (ref "U$27") (pin "26") (pinfunction "GNDA_26") (pintype "bidirectional"))
      (node (ref "U$27") (pin "27") (pinfunction "GNDA_27") (pintype "bidirectional"))
      (node (ref "U$27") (pin "28") (pinfunction "GNDA_28") (pintype "bidirectional"))
      (node (ref "U$27") (pin "29") (pinfunction "GNDA_29") (pintype "bidirectional"))
      (node (ref "U$3") (pin "P$10") (pinfunction "P$10_P$10") (pintype "bidirectional"))
      (node (ref "U$4") (pin "2") (pinfunction "GND_2") (pintype "power_in"))
      (node (ref "U$5") (pin "3") (pinfunction "S2_3") (pintype "bidirectional"))
      (node (ref "U$6") (pin "LEFT") (pinfunction "COLLECTOR_LEFT") (pintype "bidirectional"))
    )
    (net (code "6") (name "/BAT+") (class "Default")
      (node (ref "BATT") (pin "1") (pinfunction "KL_1") (pintype "passive"))
      (node (ref "ON/OFF") (pin "COM") (pinfunction "COM_COM") (pintype "bidirectional"))
      (node (ref "ON/OFF") (pin "IN1") (pinfunction "P1_IN1") (pintype "bidirectional"))
    )
    (net (code "7") (name "/BATSENSE") (class "Default")
      (node (ref "BAT") (pin "P$1") (pinfunction "P$1_P$1") (pintype "bidirectional"))
      (node (ref "BATCLAMP2") (pin "C") (pinfunction "C_C") (pintype "passive"))
      (node (ref "R17") (pin "1") (pinfunction "1_1") (pintype "passive"))
      (node (ref "R18") (pin "2") (pinfunction "2_2") (pintype "passive"))
      (node (ref "U$14") (pin "23/A9") (pinfunction "23/A9_23/A9") (pintype "bidirectional"))
    )
    (net (code "8") (name "/BB_IN") (class "Default")
      (node (ref "BB_CON") (pin "2") (pinfunction "P$2_2") (pintype "bidirectional"))
      (node (ref "U$14") (pin "31/A12") (pinfunction "31/A12_31/A12") (pintype "bidirectional"))
    )
    (net (code "9") (name "/BB_OUT") (class "Default")
      (node (ref "R19") (pin "1") (pinfunction "1_1") (pintype "passive"))
      (node (ref "U$14") (pin "32/A13") (pinfunction "32/A13_32/A13") (pintype "bidirectional"))
    )
    (net (code "10") (name "/CAP+") (class "Default")
      (node (ref "C14") (pin "+") (pinfunction "+_+") (pintype "passive"))
      (node (ref "C6") (pin "+") (pinfunction "+_+") (pintype "passive"))
      (node (ref "CAP+_TEST") (pin "P$1") (pinfunction "P$1_P$1") (pintype "bidirectional"))
      (node (ref "CHARGE_D") (pin "C") (pinfunction "C_C") (pintype "passive"))
      (node (ref "CHIP") (pin "1") (pinfunction "P$1_1") (pintype "bidirectional"))
      (node (ref "CHIP_FLY") (pin "CATHODE") (pinfunction "C_CATHODE") (pintype "passive"))
      (node (ref "KICK") (pin "1") (pinfunction "P$1_1") (pintype "bidirectional"))
      (node (ref "KICK_FLY") (pin "CATHODE") (pinfunction "C_CATHODE") (pintype "passive"))
      (node (ref "R14") (pin "2") (pinfunction "2_2") (pintype "passive"))
      (node (ref "R24") (pin "2") (pinfunction "2_2") (pintype "passive"))
      (node (ref "U$7") (pin "+") (pinfunction "D+_+") (pintype "bidirectional"))
    )
    (net (code "11") (name "/CHARGE") (class "Default")
      (node (ref "CHARGE") (pin "P$1") (pinfunction "P$1_P$1") (pintype "bidirectional"))
      (node (ref "CHARGE_LED") (pin "A") (pinfunction "A_A") (pintype "passive"))
      (node (ref "CHARGE_U") (pin "P$3") (pinfunction "CHRG_P$3") (pintype "bidirectional"))
      (node (ref "U$14") (pin "0/RX") (pinfunction "0/RX_0/RX") (pintype "bidirectional"))
    )
    (net (code "12") (name "/CHARGE_DONE") (class "Default")
      (node (ref "CHARGE_U") (pin "P$2") (pinfunction "~{DN}_P$2") (pintype "bidirectional"))
      (node (ref "DONE") (pin "P$1") (pinfunction "P$1_P$1") (pintype "bidirectional"))
      (node (ref "R12") (pin "2") (pinfunction "2_2") (pintype "passive"))
      (node (ref "R22") (pin "2") (pinfunction "2_2") (pintype "passive"))
      (node (ref "U$14") (pin "1/TX") (pinfunction "1/TX_1/TX") (pintype "bidirectional"))
    )
    (net (code "13") (name "/CHIP") (class "Default")
      (node (ref "ANDS") (pin "P$3") (pinfunction "Y2_P$3") (pintype "bidirectional"))
      (node (ref "CHIP_LED") (pin "A") (pinfunction "A_A") (pintype "passive"))
      (node (ref "U$1") (pin "3") (pinfunction "IN+_3") (pintype "input"))
    )
    (net (code "14") (name "/CHIP_ENABLE") (class "Default")
      (node (ref "ANDS") (pin "P$6") (pinfunction "B2_P$6") (pintype "bidirectional"))
      (node (ref "CE_LED") (pin "A") (pinfunction "A_A") (pintype "passive"))
      (node (ref "U$14") (pin "5") (pinfunction "5_5") (pintype "bidirectional"))
    )
    (net (code "15") (name "/CS_0") (class "Default")
      (node (ref "C22") (pin "1") (pinfunction "1_1") (pintype "passive"))
      (node (ref "R36") (pin "1") (pinfunction "1_1") (pintype "passive"))
      (node (ref "U$14") (pin "22/A8") (pinfunction "22/A8_22/A8") (pintype "bidirectional"))
    )
    (net (code "16") (name "/CS_1") (class "Default")
      (node (ref "C28") (pin "1") (pinfunction "1_1") (pintype "passive"))
      (node (ref "R65") (pin "1") (pinfunction "1_1") (pintype "passive"))
      (node (ref "U$14") (pin "21/A7") (pinfunction "21/A7_21/A7") (pintype "bidirectional"))
    )
    (net (code "17") (name "/CS_2") (class "Default")
      (node (ref "C32") (pin "1") (pinfunction "1_1") (pintype "passive"))
      (node (ref "R76") (pin "1") (pinfunction "1_1") (pintype "passive"))
      (node (ref "U$14") (pin "37/A18") (pinfunction "37/A18_37/A18") (pintype "bidirectional"))
    )
    (net (code "18") (name "/CS_3") (class "Default")
      (node (ref "C45") (pin "1") (pinfunction "1_1") (pintype "passive"))
      (node (ref "R87") (pin "1") (pinfunction "1_1") (pintype "passive"))
      (node (ref "U$14") (pin "36/A17") (pinfunction "36/A17_36/A17") (pintype "bidirectional"))
    )
    (net (code "19") (name "/CTS") (class "Default")
      (node (ref "R30") (pin "1") (pinfunction "1_1") (pintype "passive"))
      (node (ref "U$14") (pin "24") (pinfunction "24_24") (pintype "bidirectional"))
    )
    (net (code "20") (name "/DISCHARGE") (class "Default")
      (node (ref "R26") (pin "1") (pinfunction "1_1") (pintype "passive"))
      (node (ref "U$14") (pin "4/CANRX") (pinfunction "4/CANRX_4/CANRX") (pintype "bidirectional"))
    )
    (net (code "21") (name "/DIVCAP") (class "Default")
      (node (ref "CAP/100") (pin "P$1") (pinfunction "P$1_P$1") (pintype "bidirectional"))
      (node (ref "CAP_SENSE_BUF") (pin "1") (pinfunction "OUT_1") (pintype "output"))
      (node (ref "CAP_SENSE_BUF") (pin "4") (pinfunction "-IN_4") (pintype "input"))
      (node (ref "R8") (pin "1") (pinfunction "1_1") (pintype "passive"))
    )
    (net (code "22") (name "/DRIB") (class "Default")
      (node (ref "DRIB_TEST") (pin "P$1") (pinfunction "P$1_P$1") (pintype "bidirectional"))
      (node (ref "DRIB_TRAN") (pin "GATE") (pinfunction "G_GATE") (pintype "bidirectional"))
      (node (ref "U$14") (pin "6") (pinfunction "6_6") (pintype "bidirectional"))
    )
    (net (code "23") (name "/ENA_0") (class "Default")
      (node (ref "R39") (pin "1") (pinfunction "1_1") (pintype "passive"))
      (node (ref "R42") (pin "1") (pinfunction "1_1") (pintype "passive"))
      (node (ref "U$17") (pin "2") (pinfunction "GPB1_2") (pintype "bidirectional"))
    )
    (net (code "24") (name "/ENA_1") (class "Default")
      (node (ref "R67") (pin "1") (pinfunction "1_1") (pintype "passive"))
      (node (ref "R70") (pin "1") (pinfunction "1_1") (pintype "passive"))
      (node (ref "U$17") (pin "27") (pinfunction "GPA6_27") (pintype "bidirectional"))
    )
    (net (code "25") (name "/ENA_2") (class "Default")
      (node (ref "R78") (pin "1") (pinfunction "1_1") (pintype "passive"))
      (node (ref "R81") (pin "1") (pinfunction "1_1") (pintype "passive"))
      (node (ref "U$21") (pin "27") (pinfunction "GPA6_27") (pintype "bidirectional"))
    )
    (net (code "26") (name "/ENA_3") (class "Default")
      (node (ref "R89") (pin "1") (pinfunction "1_1") (pintype "passive"))
      (node (ref "R92") (pin "1") (pinfunction "1_1") (pintype "passive"))
      (node (ref "U$21") (pin "2") (pinfunction "GPB1_2") (pintype "bidirectional"))
    )
    (net (code "27") (name "/ENB_0") (class "Default")
      (node (ref "R40") (pin "1") (pinfunction "1_1") (pintype "passive"))
      (node (ref "R41") (pin "1") (pinfunction "1_1") (pintype "passive"))
      (node (ref "U$17") (pin "3") (pinfunction "GPB2_3") (pintype "bidirectional"))
    )
    (net (code "28") (name "/ENB_1") (class "Default")
      (node (ref "R68") (pin "1") (pinfunction "1_1") (pintype "passive"))
      (node (ref "R69") (pin "1") (pinfunction "1_1") (pintype "passive"))
      (node (ref "U$17") (pin "26") (pinfunction "GPA5_26") (pintype "bidirectional"))
    )
    (net (code "29") (name "/ENB_2") (class "Default")
      (node (ref "R79") (pin "1") (pinfunction "1_1") (pintype "passive"))
      (node (ref "R80") (pin "1") (pinfunction "1_1") (pintype "passive"))
      (node (ref "U$21") (pin "26") (pinfunction "GPA5_26") (pintype "bidirectional"))
    )
    (net (code "30") (name "/ENB_3") (class "Default")
      (node (ref "R90") (pin "1") (pinfunction "1_1") (pintype "passive"))
      (node (ref "R91") (pin "1") (pinfunction "1_1") (pintype "passive"))
      (node (ref "U$21") (pin "3") (pinfunction "GPB2_3") (pintype "bidirectional"))
    )
    (net (code "31") (name "/GND") (class "Default")
      (node (ref "3.3REG1") (pin "DRAIN") (pinfunction "GND_DRAIN") (pintype "bidirectional"))
      (node (ref "5REG") (pin "DRAIN") (pinfunction "GND_DRAIN") (pintype "bidirectional"))
      (node (ref "ANDS") (pin "P$4") (pinfunction "GND_P$4") (pintype "bidirectional"))
      (node (ref "BB_CON") (pin "3") (pinfunction "P$3_3") (pintype "bidirectional"))
      (node (ref "BB_CON") (pin "5") (pinfunction "P$5_5") (pintype "bidirectional"))
      (node (ref "C1") (pin "1") (pinfunction "1_1") (pintype "passive"))
      (node (ref "C10") (pin "1") (pinfunction "1_1") (pintype "passive"))
      (node (ref "C11") (pin "2") (pinfunction "2_2") (pintype "passive"))
      (node (ref "C12") (pin "2") (pinfunction "2_2") (pintype "passive"))
      (node (ref "C13") (pin "1") (pinfunction "1_1") (pintype "passive"))
      (node (ref "C15") (pin "2") (pinfunction "2_2") (pintype "passive"))
      (node (ref "C22") (pin "2") (pinfunction "2_2") (pintype "passive"))
      (node (ref "C28") (pin "2") (pinfunction "2_2") (pintype "passive"))
      (node (ref "C32") (pin "2") (pinfunction "2_2") (pintype "passive"))
      (node (ref "C33") (pin "2") (pinfunction "2_2") (pintype "passive"))
      (node (ref "C35") (pin "2") (pinfunction "2_2") (pintype "passive"))
      (node (ref "C36") (pin "2") (pinfunction "2_2") (pintype "passive"))
      (node (ref "C37") (pin "2") (pinfunction "2_2") (pintype "passive"))
      (node (ref "C38") (pin "2") (pinfunction "2_2") (pintype "passive"))
      (node (ref "C39") (pin "2") (pinfunction "2_2") (pintype "passive"))
      (node (ref "C40") (pin "2") (pinfunction "2_2") (pintype "passive"))
      (node (ref "C41") (pin "2") (pinfunction "2_2") (pintype "passive"))
      (node (ref "C45") (pin "2") (pinfunction "2_2") (pintype "passive"))
      (node (ref "C8") (pin "2") (pinfunction "2_2") (pintype "passive"))
      (node (ref "C9") (pin "2") (pinfunction "2_2") (pintype "passive"))
      (node (ref "GND") (pin "P$1") (pinfunction "P$1_P$1") (pintype "bidirectional"))
      (node (ref "JP1") (pin "3") (pinfunction "3_3") (pintype "passive"))
      (node (ref "JP2") (pin "3") (pinfunction "3_3") (pintype "passive"))
      (node (ref "JP3") (pin "3") (pinfunction "3_3") (pintype "passive"))
      (node (ref "JP4") (pin "3") (pinfunction "3_3") (pintype "passive"))
      (node (ref "R10") (pin "1") (pinfunction "1_1") (pintype "passive"))
      (node (ref "R11") (pin "2") (pinfunction "2_2") (pintype "passive"))
      (node (ref "R4") (pin "2") (pinfunction "2_2") (pintype "passive"))
      (node (ref "R45") (pin "2") (pinfunction "2_2") (pintype "passive"))
      (node (ref "R47") (pin "2") (pinfunction "2_2") (pintype "passive"))
      (node (ref "R49") (pin "2") (pinfunction "2_2") (pintype "passive"))
      (node (ref "R5") (pin "2") (pinfunction "2_2") (pintype "passive"))
      (node (ref "R51") (pin "2") (pinfunction "2_2") (pintype "passive"))
      (node (ref "R53") (pin "2") (pinfunction "2_2") (pintype "passive"))
      (node (ref "R55") (pin "2") (pinfunction "2_2") (pintype "passive"))
      (node (ref "R57") (pin "2") (pinfunction "2_2") (pintype "passive"))
      (node (ref "R59") (pin "2") (pinfunction "2_2") (pintype "passive"))
      (node (ref "R60") (pin "1") (pinfunction "1_1") (pintype "passive"))
      (node (ref "R61") (pin "1") (pinfunction "1_1") (pintype "passive"))
      (node (ref "R71") (pin "1") (pinfunction "1_1") (pintype "passive"))
      (node (ref "R72") (pin "1") (pinfunction "1_1") (pintype "passive"))
      (node (ref "R82") (pin "1") (pinfunction "1_1") (pintype "passive"))
      (node (ref "R83") (pin "1") (pinfunction "1_1") (pintype "passive"))
      (node (ref "R9") (pin "1") (pinfunction "1_1") (pintype "passive"))
      (node (ref "R93") (pin "1") (pinfunction "1_1") (pintype "passive"))
      (node (ref "R94") (pin "1") (pinfunction "1_1") (pintype "passive"))
      (node (ref "U$14") (pin "AGND") (pinfunction "AGND_AGND") (pintype "bidirectional"))
      (node (ref "U$14") (pin "GND") (pinfunction "GND_GND") (pintype "bidirectional"))
      (node (ref "U$14") (pin "GND2") (pinfunction "GND2_GND2") (pintype "bidirectional"))
      (node (ref "U$15") (pin "10") (pinfunction "GND_10") (pintype "power_in"))
      (node (ref "U$17") (pin "10") (pinfunction "VSS_10") (pintype "bidirectional"))
      (node (ref "U$17") (pin "15") (pinfunction "A0_15") (pintype "bidirectional"))
      (node (ref "U$17") (pin "16") (pinfunction "A1_16") (pintype "bidirectional"))
      (node (ref "U$17") (pin "17") (pinfunction "A2_17") (pintype "bidirectional"))
      (node (ref "U$18") (pin "1") (pinfunction "EOUT_1") (pintype "bidirectional"))
      (node (ref "U$18") (pin "4") (pinfunction "VCC_4") (pintype "bidirectional"))
      (node (ref "U$19") (pin "2") (pinfunction "P$2_2") (pintype "bidirectional"))
      (node (ref "U$21") (pin "10") (pinfunction "VSS_10") (pintype "bidirectional"))
      (node (ref "U$21") (pin "15") (pinfunction "A0_15") (pintype "bidirectional"))
      (node (ref "U$21") (pin "16") (pinfunction "A1_16") (pintype "bidirectional"))
      (node (ref "U$22") (pin "S") (pinfunction "S_S") (pintype "bidirectional"))
      (node (ref "U$5") (pin "2") (pinfunction "LED-_2") (pintype "bidirectional"))
      (node (ref "U$8") (pin "1") (pinfunction "GND_1") (pintype "bidirectional"))
    )
    (net (code "32") (name "/INA_0") (class "Default")
      (node (ref "R63") (pin "2") (pinfunction "2_2") (pintype "passive"))
      (node (ref "U$17") (pin "1") (pinfunction "GPB0_1") (pintype "bidirectional"))
    )
    (net (code "33") (name "/INA_1") (class "Default")
      (node (ref "R74") (pin "2") (pinfunction "2_2") (pintype "passive"))
      (node (ref "U$17") (pin "28") (pinfunction "GPA7_28") (pintype "bidirectional"))
    )
    (net (code "34") (name "/INA_2") (class "Default")
      (node (ref "R85") (pin "2") (pinfunction "2_2") (pintype "passive"))
      (node (ref "U$21") (pin "28") (pinfunction "GPA7_28") (pintype "bidirectional"))
    )
    (net (code "35") (name "/INA_3") (class "Default")
      (node (ref "R96") (pin "2") (pinfunction "2_2") (pintype "passive"))
      (node (ref "U$21") (pin "1") (pinfunction "GPB0_1") (pintype "bidirectional"))
    )
    (net (code "36") (name "/INB_0") (class "Default")
      (node (ref "R62") (pin "2") (pinfunction "2_2") (pintype "passive"))
      (node (ref "U$17") (pin "4") (pinfunction "GPB3_4") (pintype "bidirectional"))
    )
    (net (code "37") (name "/INB_1") (class "Default")
      (node (ref "R73") (pin "2") (pinfunction "2_2") (pintype "passive"))
      (node (ref "U$17") (pin "25") (pinfunction "GPA4_25") (pintype "bidirectional"))
    )
    (net (code "38") (name "/INB_2") (class "Default")
      (node (ref "R84") (pin "2") (pinfunction "2_2") (pintype "passive"))
      (node (ref "U$21") (pin "25") (pinfunction "GPA4_25") (pintype "bidirectional"))
    )
    (net (code "39") (name "/INB_3") (class "Default")
      (node (ref "R95") (pin "2") (pinfunction "2_2") (pintype "passive"))
      (node (ref "U$21") (pin "4") (pinfunction "GPB3_4") (pintype "bidirectional"))
    )
    (net (code "40") (name "/INT1") (class "Default")
      (node (ref "U$14") (pin "9/CS") (pinfunction "9/CS_9/CS") (pintype "bidirectional"))
      (node (ref "U$17") (pin "20") (pinfunction "INTA_20") (pintype "bidirectional"))
    )
    (net (code "41") (name "/INT2") (class "Default")
      (node (ref "U$14") (pin "39/A20") (pinfunction "39/A20_39/A20") (pintype "bidirectional"))
      (node (ref "U$21") (pin "20") (pinfunction "INTA_20") (pintype "bidirectional"))
    )
    (net (code "42") (name "/KICK") (class "Default")
      (node (ref "ANDS") (pin "P$7") (pinfunction "Y1_P$7") (pintype "bidirectional"))
      (node (ref "KICK_LED") (pin "A") (pinfunction "A_A") (pintype "passive"))
      (node (ref "U$4") (pin "3") (pinfunction "IN+_3") (pintype "input"))
    )
    (net (code "43") (name "/KICK_ENABLE") (class "Default")
      (node (ref "ANDS") (pin "P$2") (pinfunction "B1_P$2") (pintype "bidirectional"))
      (node (ref "KE_LED") (pin "A") (pinfunction "A_A") (pintype "passive"))
      (node (ref "U$14") (pin "7") (pinfunction "7_7") (pintype "bidirectional"))
    )
    (net (code "44") (name "/KICK_REF") (class "Default")
      (node (ref "R37") (pin "1") (pinfunction "1_1") (pintype "passive"))
      (node (ref "U$14") (pin "A22/DAC1") (pinfunction "A22/DAC1_A22/DAC1") (pintype "bidirectional"))
    )
    (net (code "45") (name "/M1QA-1") (class "Default")
      (node (ref "JP1") (pin "5") (pinfunction "5_5") (pintype "passive"))
      (node (ref "R58") (pin "2") (pinfunction "2_2") (pintype "passive"))
    )
    (net (code "46") (name "/M1QA-1OUT") (class "Default")
      (node (ref "R58") (pin "1") (pinfunction "1_1") (pintype "passive"))
      (node (ref "R59") (pin "1") (pinfunction "1_1") (pintype "passive"))
      (node (ref "U$14") (pin "17/A3") (pinfunction "17/A3_17/A3") (pintype "bidirectional"))
    )
    (net (code "47") (name "/M1QA-2") (class "Default")
      (node (ref "JP2") (pin "5") (pinfunction "5_5") (pintype "passive"))
      (node (ref "R52") (pin "2") (pinfunction "2_2") (pintype "passive"))
    )
    (net (code "48") (name "/M1QA-2OUT") (class "Default")
      (node (ref "R52") (pin "1") (pinfunction "1_1") (pintype "passive"))
      (node (ref "R53") (pin "1") (pinfunction "1_1") (pintype "passive"))
      (node (ref "U$14") (pin "27") (pinfunction "27_27") (pintype "bidirectional"))
    )
    (net (code "49") (name "/M1QA-3") (class "Default")
      (node (ref "JP3") (pin "5") (pinfunction "5_5") (pintype "passive"))
      (node (ref "R54") (pin "2") (pinfunction "2_2") (pintype "passive"))
    )
    (net (code "50") (name "/M1QA-3OUT") (class "Default")
      (node (ref "R54") (pin "1") (pinfunction "1_1") (pintype "passive"))
      (node (ref "R55") (pin "1") (pinfunction "1_1") (pintype "passive"))
      (node (ref "U$14") (pin "15/A1") (pinfunction "15/A1_15/A1") (pintype "bidirectional"))
    )
    (net (code "51") (name "/M1QA-4") (class "Default")
      (node (ref "JP4") (pin "5") (pinfunction "5_5") (pintype "passive"))
      (node (ref "R56") (pin "2") (pinfunction "2_2") (pintype "passive"))
    )
    (net (code "52") (name "/M1QA-4OUT") (class "Default")
      (node (ref "R56") (pin "1") (pinfunction "1_1") (pintype "passive"))
      (node (ref "R57") (pin "1") (pinfunction "1_1") (pintype "passive"))
      (node (ref "U$14") (pin "25") (pinfunction "25_25") (pintype "bidirectional"))
    )
    (net (code "53") (name "/M1QB-1") (class "Default")
      (node (ref "JP1") (pin "6") (pinfunction "6_6") (pintype "passive"))
      (node (ref "R50") (pin "2") (pinfunction "2_2") (pintype "passive"))
    )
    (net (code "54") (name "/M1QB-1OUT") (class "Default")
      (node (ref "R50") (pin "1") (pinfunction "1_1") (pintype "passive"))
      (node (ref "R51") (pin "1") (pinfunction "1_1") (pintype "passive"))
      (node (ref "U$14") (pin "16/A2") (pinfunction "16/A2_16/A2") (pintype "bidirectional"))
    )
    (net (code "55") (name "/M1QB-2") (class "Default")
      (node (ref "JP2") (pin "6") (pinfunction "6_6") (pintype "passive"))
      (node (ref "R44") (pin "2") (pinfunction "2_2") (pintype "passive"))
    )
    (net (code "56") (name "/M1QB-2OUT") (class "Default")
      (node (ref "R44") (pin "1") (pinfunction "1_1") (pintype "passive"))
      (node (ref "R45") (pin "1") (pinfunction "1_1") (pintype "passive"))
      (node (ref "U$14") (pin "28") (pinfunction "28_28") (pintype "bidirectional"))
    )
    (net (code "57") (name "/M1QB-3") (class "Default")
      (node (ref "JP3") (pin "6") (pinfunction "6_6") (pintype "passive"))
      (node (ref "R46") (pin "2") (pinfunction "2_2") (pintype "passive"))
    )
    (net (code "58") (name "/M1QB-3OUT") (class "Default")
      (node (ref "R46") (pin "1") (pinfunction "1_1") (pintype "passive"))
      (node (ref "R47") (pin "1") (pinfunction "1_1") (pintype "passive"))
      (node (ref "U$14") (pin "14/A0") (pinfunction "14/A0_14/A0") (pintype "bidirectional"))
    )
    (net (code "59") (name "/M1QB-4") (class "Default")
      (node (ref "JP4") (pin "6") (pinfunction "6_6") (pintype "passive"))
      (node (ref "R48") (pin "2") (pinfunction "2_2") (pintype "passive"))
    )
    (net (code "60") (name "/M1QB-4OUT") (class "Default")
      (node (ref "R48") (pin "1") (pinfunction "1_1") (pintype "passive"))
      (node (ref "R49") (pin "1") (pinfunction "1_1") (pintype "passive"))
      (node (ref "U$14") (pin "26") (pinfunction "26_26") (pintype "bidirectional"))
    )
    (net (code "61") (name "/N$38") (class "Default")
      (node (ref "C13") (pin "2") (pinfunction "2_2") (pintype "passive"))
      (node (ref "R32") (pin "1") (pinfunction "1_1") (pintype "passive"))
      (node (ref "U$8") (pin "7") (pinfunction "VREF2_7") (pintype "bidirectional"))
      (node (ref "U$8") (pin "8") (pinfunction "EN_8") (pintype "bidirectional"))
    )
    (net (code "62") (name "/OUTA_0") (class "Default")
      (node (ref "GREEN_DIR") (pin "C") (pinfunction "C_C") (pintype "passive"))
      (node (ref "JP1") (pin "1") (pinfunction "1_1") (pintype "passive"))
      (node (ref "RED_DIR") (pin "A") (pinfunction "A_A") (pintype "passive"))
      (node (ref "U$16") (pin "1") (pinfunction "OUTA_1") (pintype "bidirectional"))
      (node (ref "U$16") (pin "24") (pinfunction "OUTA_24") (pintype "bidirectional"))
      (node (ref "U$16") (pin "25") (pinfunction "OUTA_25") (pintype "bidirectional"))
      (node (ref "U$16") (pin "30") (pinfunction "OUTA_30") (pintype "bidirectional"))
      (node (ref "U$16") (pin "OUTA") (pinfunction "OUTA_OUTA") (pintype "bidirectional"))
      (node (ref "U$16") (pin "OUTA@1") (pinfunction "OUTA_OUTA@1") (pintype "bidirectional"))
    )
    (net (code "63") (name "/OUTA_1") (class "Default")
      (node (ref "GREEN_DIR1") (pin "C") (pinfunction "C_C") (pintype "passive"))
      (node (ref "JP2") (pin "1") (pinfunction "1_1") (pintype "passive"))
      (node (ref "RED_DIR1") (pin "A") (pinfunction "A_A") (pintype "passive"))
      (node (ref "U$23") (pin "1") (pinfunction "OUTA_1") (pintype "bidirectional"))
      (node (ref "U$23") (pin "24") (pinfunction "OUTA_24") (pintype "bidirectional"))
      (node (ref "U$23") (pin "25") (pinfunction "OUTA_25") (pintype "bidirectional"))
      (node (ref "U$23") (pin "30") (pinfunction "OUTA_30") (pintype "bidirectional"))
      (node (ref "U$23") (pin "OUTA") (pinfunction "OUTA_OUTA") (pintype "bidirectional"))
      (node (ref "U$23") (pin "OUTA@1") (pinfunction "OUTA_OUTA@1") (pintype "bidirectional"))
    )
    (net (code "64") (name "/OUTA_2") (class "Default")
      (node (ref "GREEN_DIR2") (pin "C") (pinfunction "C_C") (pintype "passive"))
      (node (ref "JP3") (pin "1") (pinfunction "1_1") (pintype "passive"))
      (node (ref "RED_DIR2") (pin "A") (pinfunction "A_A") (pintype "passive"))
      (node (ref "U$25") (pin "1") (pinfunction "OUTA_1") (pintype "bidirectional"))
      (node (ref "U$25") (pin "24") (pinfunction "OUTA_24") (pintype "bidirectional"))
      (node (ref "U$25") (pin "25") (pinfunction "OUTA_25") (pintype "bidirectional"))
      (node (ref "U$25") (pin "30") (pinfunction "OUTA_30") (pintype "bidirectional"))
      (node (ref "U$25") (pin "OUTA") (pinfunction "OUTA_OUTA") (pintype "bidirectional"))
      (node (ref "U$25") (pin "OUTA@1") (pinfunction "OUTA_OUTA@1") (pintype "bidirectional"))
    )
    (net (code "65") (name "/OUTA_3") (class "Default")
      (node (ref "GREEN_DIR3") (pin "C") (pinfunction "C_C") (pintype "passive"))
      (node (ref "JP4") (pin "1") (pinfunction "1_1") (pintype "passive"))
      (node (ref "RED_DIR3") (pin "A") (pinfunction "A_A") (pintype "passive"))
      (node (ref "U$27") (pin "1") (pinfunction "OUTA_1") (pintype "bidirectional"))
      (node (ref "U$27") (pin "24") (pinfunction "OUTA_24") (pintype "bidirectional"))
      (node (ref "U$27") (pin "25") (pinfunction "OUTA_25") (pintype "bidirectional"))
      (node (ref "U$27") (pin "30") (pinfunction "OUTA_30") (pintype "bidirectional"))
      (node (ref "U$27") (pin "OUTA") (pinfunction "OUTA_OUTA") (pintype "bidirectional"))
      (node (ref "U$27") (pin "OUTA@1") (pinfunction "OUTA_OUTA@1") (pintype "bidirectional"))
    )
    (net (code "66") (name "/OUTB_0") (class "Default")
      (node (ref "JP1") (pin "2") (pinfunction "2_2") (pintype "passive"))
      (node (ref "R38") (pin "1") (pinfunction "1_1") (pintype "passive"))
      (node (ref "U$16") (pin "15") (pinfunction "OUTB_15") (pintype "bidirectional"))
      (node (ref "U$16") (pin "16") (pinfunction "OUTB_16") (pintype "bidirectional"))
      (node (ref "U$16") (pin "21") (pinfunction "OUTB_21") (pintype "bidirectional"))
      (node (ref "U$16") (pin "22") (pinfunction "OUTB_22") (pintype "bidirectional"))
      (node (ref "U$16") (pin "OUTB") (pinfunction "OUTB_OUTB") (pintype "bidirectional"))
      (node (ref "U$16") (pin "OUTB@1") (pinfunction "OUTB_OUTB@1") (pintype "bidirectional"))
    )
    (net (code "67") (name "/OUTB_1") (class "Default")
      (node (ref "JP2") (pin "2") (pinfunction "2_2") (pintype "passive"))
      (node (ref "R66") (pin "1") (pinfunction "1_1") (pintype "passive"))
      (node (ref "U$23") (pin "15") (pinfunction "OUTB_15") (pintype "bidirectional"))
      (node (ref "U$23") (pin "16") (pinfunction "OUTB_16") (pintype "bidirectional"))
      (node (ref "U$23") (pin "21") (pinfunction "OUTB_21") (pintype "bidirectional"))
      (node (ref "U$23") (pin "22") (pinfunction "OUTB_22") (pintype "bidirectional"))
      (node (ref "U$23") (pin "OUTB") (pinfunction "OUTB_OUTB") (pintype "bidirectional"))
      (node (ref "U$23") (pin "OUTB@1") (pinfunction "OUTB_OUTB@1") (pintype "bidirectional"))
    )
    (net (code "68") (name "/OUTB_2") (class "Default")
      (node (ref "JP3") (pin "2") (pinfunction "2_2") (pintype "passive"))
      (node (ref "R77") (pin "1") (pinfunction "1_1") (pintype "passive"))
      (node (ref "U$25") (pin "15") (pinfunction "OUTB_15") (pintype "bidirectional"))
      (node (ref "U$25") (pin "16") (pinfunction "OUTB_16") (pintype "bidirectional"))
      (node (ref "U$25") (pin "21") (pinfunction "OUTB_21") (pintype "bidirectional"))
      (node (ref "U$25") (pin "22") (pinfunction "OUTB_22") (pintype "bidirectional"))
      (node (ref "U$25") (pin "OUTB") (pinfunction "OUTB_OUTB") (pintype "bidirectional"))
      (node (ref "U$25") (pin "OUTB@1") (pinfunction "OUTB_OUTB@1") (pintype "bidirectional"))
    )
    (net (code "69") (name "/OUTB_3") (class "Default")
      (node (ref "JP4") (pin "2") (pinfunction "2_2") (pintype "passive"))
      (node (ref "R88") (pin "1") (pinfunction "1_1") (pintype "passive"))
      (node (ref "U$27") (pin "15") (pinfunction "OUTB_15") (pintype "bidirectional"))
      (node (ref "U$27") (pin "16") (pinfunction "OUTB_16") (pintype "bidirectional"))
      (node (ref "U$27") (pin "21") (pinfunction "OUTB_21") (pintype "bidirectional"))
      (node (ref "U$27") (pin "22") (pinfunction "OUTB_22") (pintype "bidirectional"))
      (node (ref "U$27") (pin "OUTB") (pinfunction "OUTB_OUTB") (pintype "bidirectional"))
      (node (ref "U$27") (pin "OUTB@1") (pinfunction "OUTB_OUTB@1") (pintype "bidirectional"))
    )
    (net (code "70") (name "/PWM0") (class "Default")
      (node (ref "R35") (pin "1") (pinfunction "1_1") (pintype "passive"))
      (node (ref "R60") (pin "2") (pinfunction "2_2") (pintype "passive"))
      (node (ref "U$14") (pin "2") (pinfunction "2_2") (pintype "bidirectional"))
    )
    (net (code "71") (name "/PWM1") (class "Default")
      (node (ref "R64") (pin "1") (pinfunction "1_1") (pintype "passive"))
      (node (ref "R71") (pin "2") (pinfunction "2_2") (pintype "passive"))
      (node (ref "U$14") (pin "3/CANTX") (pinfunction "3/CANTX_3/CANTX") (pintype "bidirectional"))
    )
    (net (code "72") (name "/PWM2") (class "Default")
      (node (ref "R75") (pin "1") (pinfunction "1_1") (pintype "passive"))
      (node (ref "R82") (pin "2") (pinfunction "2_2") (pintype "passive"))
      (node (ref "U$14") (pin "10/CS") (pinfunction "10/CS_10/CS") (pintype "bidirectional"))
    )
    (net (code "73") (name "/PWM3") (class "Default")
      (node (ref "R86") (pin "1") (pinfunction "1_1") (pintype "passive"))
      (node (ref "R93") (pin "2") (pinfunction "2_2") (pintype "passive"))
      (node (ref "U$14") (pin "29") (pinfunction "29_29") (pintype "bidirectional"))
    )
    (net (code "74") (name "/RTS") (class "Default")
      (node (ref "R28") (pin "1") (pinfunction "1_1") (pintype "passive"))
      (node (ref "U$14") (pin "35/A16") (pinfunction "35/A16_35/A16") (pintype "bidirectional"))
    )
    (net (code "75") (name "/RX") (class "Default")
      (node (ref "U$14") (pin "34/A15") (pinfunction "34/A15_34/A15") (pintype "bidirectional"))
      (node (ref "U$15") (pin "2") (pinfunction "DOUT_2") (pintype "output"))
    )
    (net (code "76") (name "/SCL") (class "Default")
      (node (ref "R27") (pin "1") (pinfunction "1_1") (pintype "passive"))
      (node (ref "U$14") (pin "19/A5/SCL") (pinfunction "19/A5/SCL_19/A5/SCL") (pintype "bidirectional"))
      (node (ref "U$8") (pin "3") (pinfunction "SCL1_3") (pintype "bidirectional"))
    )
    (net (code "77") (name "/SCL-H") (class "Default")
      (node (ref "R33") (pin "1") (pinfunction "1_1") (pintype "passive"))
      (node (ref "U$17") (pin "12") (pinfunction "SCK_12") (pintype "bidirectional"))
      (node (ref "U$21") (pin "12") (pinfunction "SCK_12") (pintype "bidirectional"))
      (node (ref "U$8") (pin "6") (pinfunction "SCL2_6") (pintype "bidirectional"))
    )
    (net (code "78") (name "/SDA") (class "Default")
      (node (ref "R7") (pin "1") (pinfunction "1_1") (pintype "passive"))
      (node (ref "U$14") (pin "18/A4/SDA") (pinfunction "18/A4/SDA_18/A4/SDA") (pintype "bidirectional"))
      (node (ref "U$8") (pin "4") (pinfunction "SDA1_4") (pintype "bidirectional"))
    )
    (net (code "79") (name "/SDA-H") (class "Default")
      (node (ref "R34") (pin "1") (pinfunction "1_1") (pintype "passive"))
      (node (ref "U$17") (pin "13") (pinfunction "SDA_13") (pintype "bidirectional"))
      (node (ref "U$21") (pin "13") (pinfunction "SDA_13") (pintype "bidirectional"))
      (node (ref "U$8") (pin "5") (pinfunction "SDA2_5") (pintype "bidirectional"))
    )
    (net (code "80") (name "/TX") (class "Default")
      (node (ref "U$14") (pin "33/A14") (pinfunction "33/A14_33/A14") (pintype "bidirectional"))
      (node (ref "U$15") (pin "3") (pinfunction "DIN_3") (pintype "input"))
    )
    (net (code "81") (name "/XBRST") (class "Default")
      (node (ref "U$15") (pin "5") (pinfunction "RESET_5") (pintype "input"))
    )
    (net (code "82") (name "Net-(ANDS-A1)") (class "Default")
      (node (ref "ANDS") (pin "P$1") (pinfunction "A1_P$1") (pintype "bidirectional"))
      (node (ref "ANDS") (pin "P$5") (pinfunction "A2_P$5") (pintype "bidirectional"))
      (node (ref "R29") (pin "2") (pinfunction "2_2") (pintype "passive"))
      (node (ref "U$18") (pin "7") (pinfunction "COUT_7") (pintype "bidirectional"))
      (node (ref "U$22") (pin "G") (pinfunction "G_G") (pintype "bidirectional"))
    )
    (net (code "83") (name "Net-(BB_CON-P$1)") (class "Default")
      (node (ref "BB_CON") (pin "1") (pinfunction "P$1_1") (pintype "bidirectional"))
      (node (ref "R20") (pin "2") (pinfunction "2_2") (pintype "passive"))
    )
    (net (code "84") (name "Net-(BB_CON-P$4)") (class "Default")
      (node (ref "BB_CON") (pin "4") (pinfunction "P$4_4") (pintype "bidirectional"))
      (node (ref "R19") (pin "2") (pinfunction "2_2") (pintype "passive"))
    )
    (net (code "85") (name "Net-(CAP_SENSE_BUF-+IN)") (class "Default")
      (node (ref "CAP_SENSE_BUF") (pin "3") (pinfunction "+IN_3") (pintype "input"))
      (node (ref "CLAMP1") (pin "A") (pinfunction "A_A") (pintype "passive"))
      (node (ref "CLAMP2") (pin "C") (pinfunction "C_C") (pintype "passive"))
      (node (ref "R14") (pin "1") (pinfunction "1_1") (pintype "passive"))
      (node (ref "R15") (pin "2") (pinfunction "2_2") (pintype "passive"))
    )
    (net (code "86") (name "Net-(CE_LED-PadC)") (class "Default")
      (node (ref "CE_LED") (pin "C") (pinfunction "C_C") (pintype "passive"))
      (node (ref "R5") (pin "1") (pinfunction "1_1") (pintype "passive"))
    )
    (net (code "87") (name "Net-(CHARGE_D-PadA)") (class "Default")
      (node (ref "CHARGE_D") (pin "A") (pinfunction "A_A") (pintype "passive"))
      (node (ref "U$3") (pin "P$1") (pinfunction "P$1_P$1") (pintype "bidirectional"))
    )
    (net (code "88") (name "Net-(CHARGE_LED-PadC)") (class "Default")
      (node (ref "CHARGE_LED") (pin "C") (pinfunction "C_C") (pintype "passive"))
      (node (ref "R11") (pin "1") (pinfunction "1_1") (pintype "passive"))
    )
    (net (code "89") (name "Net-(CHARGE_U-GATE)") (class "Default")
      (node (ref "CHARGE_U") (pin "P$7") (pinfunction "GATE_P$7") (pintype "bidirectional"))
      (node (ref "R43") (pin "1") (pinfunction "1_1") (pintype "passive"))
    )
    (net (code "90") (name "Net-(CHARGE_U-RBG)") (class "Default")
      (node (ref "C19") (pin "1") (pinfunction "1_1") (pintype "passive"))
      (node (ref "CHARGE_U") (pin "P$10") (pinfunction "RBG_P$10") (pintype "bidirectional"))
      (node (ref "RBG") (pin "2") (pinfunction "2_2") (pintype "passive"))
    )
    (net (code "91") (name "Net-(CHARGE_U-RDCM)") (class "Default")
      (node (ref "CHARGE_U") (pin "P$8") (pinfunction "RDCM_P$8") (pintype "bidirectional"))
      (node (ref "R31") (pin "1") (pinfunction "1_1") (pintype "passive"))
    )
    (net (code "92") (name "Net-(CHARGE_U-RV)") (class "Default")
      (node (ref "CHARGE_U") (pin "P$9") (pinfunction "RV_P$9") (pintype "bidirectional"))
      (node (ref "RVOUT") (pin "1") (pinfunction "1_1") (pintype "passive"))
    )
    (net (code "93") (name "Net-(CHARGE_U-SRC)") (class "Default")
      (node (ref "CHARGE_U") (pin "P$6") (pinfunction "SRC_P$6") (pintype "bidirectional"))
      (node (ref "RSENSE") (pin "2") (pinfunction "2_2") (pintype "passive"))
      (node (ref "SWITCH_Q") (pin "SOURCE") (pinfunction "S_SOURCE") (pintype "bidirectional"))
    )
    (net (code "94") (name "Net-(CHIP-P$2)") (class "Default")
      (node (ref "CHIP") (pin "2") (pinfunction "P$2_2") (pintype "bidirectional"))
      (node (ref "CHIP_FLY") (pin "ANODE") (pinfunction "A_ANODE") (pintype "passive"))
      (node (ref "Q2") (pin "C@1") (pinfunction "C_C@1") (pintype "passive"))
      (node (ref "Q2") (pin "C@2") (pinfunction "C_C@2") (pintype "passive"))
    )
    (net (code "95") (name "Net-(CHIP_LED-PadC)") (class "Default")
      (node (ref "CHIP_LED") (pin "C") (pinfunction "C_C") (pintype "passive"))
      (node (ref "R10") (pin "2") (pinfunction "2_2") (pintype "passive"))
    )
    (net (code "96") (name "Net-(DONE_LED-PadC)") (class "Default")
      (node (ref "DONE_LED") (pin "C") (pinfunction "C_C") (pintype "passive"))
      (node (ref "R12") (pin "1") (pinfunction "1_1") (pintype "passive"))
    )
    (net (code "97") (name "Net-(DRIB-P$2)") (class "Default")
      (node (ref "DRIB") (pin "2") (pinfunction "P$2_2") (pintype "bidirectional"))
      (node (ref "DRIB_TRAN") (pin "DRAIN") (pinfunction "D_DRAIN") (pintype "bidirectional"))
    )
    (net (code "98") (name "Net-(GREEN_DIR-PadA)") (class "Default")
      (node (ref "GREEN_DIR") (pin "A") (pinfunction "A_A") (pintype "passive"))
      (node (ref "R38") (pin "2") (pinfunction "2_2") (pintype "passive"))
      (node (ref "RED_DIR") (pin "C") (pinfunction "C_C") (pintype "passive"))
    )
    (net (code "99") (name "Net-(GREEN_DIR1-PadA)") (class "Default")
      (node (ref "GREEN_DIR1") (pin "A") (pinfunction "A_A") (pintype "passive"))
      (node (ref "R66") (pin "2") (pinfunction "2_2") (pintype "passive"))
      (node (ref "RED_DIR1") (pin "C") (pinfunction "C_C") (pintype "passive"))
    )
    (net (code "100") (name "Net-(GREEN_DIR2-PadA)") (class "Default")
      (node (ref "GREEN_DIR2") (pin "A") (pinfunction "A_A") (pintype "passive"))
      (node (ref "R77") (pin "2") (pinfunction "2_2") (pintype "passive"))
      (node (ref "RED_DIR2") (pin "C") (pinfunction "C_C") (pintype "passive"))
    )
    (net (code "101") (name "Net-(GREEN_DIR3-PadA)") (class "Default")
      (node (ref "GREEN_DIR3") (pin "A") (pinfunction "A_A") (pintype "passive"))
      (node (ref "R88") (pin "2") (pinfunction "2_2") (pintype "passive"))
      (node (ref "RED_DIR3") (pin "C") (pinfunction "C_C") (pintype "passive"))
    )
    (net (code "102") (name "Net-(KE_LED-PadC)") (class "Default")
      (node (ref "KE_LED") (pin "C") (pinfunction "C_C") (pintype "passive"))
      (node (ref "R4") (pin "1") (pinfunction "1_1") (pintype "passive"))
    )
    (net (code "103") (name "Net-(KICK-P$2)") (class "Default")
      (node (ref "KICK") (pin "2") (pinfunction "P$2_2") (pintype "bidirectional"))
      (node (ref "KICK_FLY") (pin "ANODE") (pinfunction "A_ANODE") (pintype "passive"))
      (node (ref "Q1") (pin "C@1") (pinfunction "C_C@1") (pintype "passive"))
      (node (ref "Q1") (pin "C@2") (pinfunction "C_C@2") (pintype "passive"))
    )
    (net (code "104") (name "Net-(KICK_LED-PadC)") (class "Default")
      (node (ref "KICK_LED") (pin "C") (pinfunction "C_C") (pintype "passive"))
      (node (ref "R9") (pin "2") (pinfunction "2_2") (pintype "passive"))
    )
    (net (code "105") (name "Net-(KICK_READY-PadC)") (class "Default")
      (node (ref "KICK_READY") (pin "C") (pinfunction "C_C") (pintype "passive"))
      (node (ref "R6") (pin "2") (pinfunction "2_2") (pintype "passive"))
    )
    (net (code "106") (name "Net-(NEON-Pad1)") (class "Default")
      (node (ref "NEON") (pin "1") (pinfunction "1_1") (pintype "passive"))
      (node (ref "R24") (pin "1") (pinfunction "1_1") (pintype "passive"))
    )
    (net (code "107") (name "Net-(PW_LED1-PadC)") (class "Default")
      (node (ref "PW_LED1") (pin "C") (pinfunction "C_C") (pintype "passive"))
      (node (ref "R21") (pin "2") (pinfunction "2_2") (pintype "passive"))
    )
    (net (code "108") (name "Net-(Q1-PadG)") (class "Default")
      (node (ref "Q1") (pin "G") (pinfunction "G_G") (pintype "passive"))
      (node (ref "R1") (pin "2") (pinfunction "2_2") (pintype "passive"))
    )
    (net (code "109") (name "Net-(Q2-PadG)") (class "Default")
      (node (ref "Q2") (pin "G") (pinfunction "G_G") (pintype "passive"))
      (node (ref "R2") (pin "2") (pinfunction "2_2") (pintype "passive"))
    )
    (net (code "110") (name "Net-(R6-Pad1)") (class "Default")
      (node (ref "R6") (pin "1") (pinfunction "1_1") (pintype "passive"))
      (node (ref "U$22") (pin "D") (pinfunction "D_D") (pintype "bidirectional"))
    )
    (net (code "111") (name "Net-(SWITCH_Q-D)") (class "Default")
      (node (ref "DRAIN") (pin "P$1") (pinfunction "P$1_P$1") (pintype "bidirectional"))
      (node (ref "R31") (pin "2") (pinfunction "2_2") (pintype "passive"))
      (node (ref "RVOUT") (pin "2") (pinfunction "2_2") (pintype "passive"))
      (node (ref "SWITCH_Q") (pin "DRAIN") (pinfunction "D_DRAIN") (pintype "bidirectional"))
      (node (ref "U$3") (pin "P$6") (pinfunction "P$6_P$6") (pintype "bidirectional"))
      (node (ref "U$3") (pin "P$7") (pinfunction "P$7_P$7") (pintype "bidirectional"))
    )
    (net (code "112") (name "Net-(SWITCH_Q-G)") (class "Default")
      (node (ref "GATE") (pin "P$1") (pinfunction "P$1_P$1") (pintype "bidirectional"))
      (node (ref "R43") (pin "2") (pinfunction "2_2") (pintype "passive"))
      (node (ref "SWITCH_Q") (pin "GATE") (pinfunction "G_GATE") (pintype "bidirectional"))
    )
    (net (code "113") (name "Net-(U$1-OUT)") (class "Default")
      (node (ref "R2") (pin "1") (pinfunction "1_1") (pintype "passive"))
      (node (ref "U$1") (pin "5") (pinfunction "OUT_5") (pintype "output"))
    )
    (net (code "114") (name "Net-(U$2-DRAIN)") (class "Default")
      (node (ref "U$2") (pin "TAB") (pinfunction "DRAIN_TAB") (pintype "bidirectional"))
      (node (ref "U$7") (pin "-") (pinfunction "D-_-") (pintype "bidirectional"))
    )
    (net (code "115") (name "Net-(U$2-GATE)") (class "Default")
      (node (ref "R25") (pin "1") (pinfunction "1_1") (pintype "passive"))
      (node (ref "U$2") (pin "LOWER_LEFT") (pinfunction "GATE_LOWER_LEFT") (pintype "bidirectional"))
    )
    (net (code "116") (name "Net-(U$2-SOURCE)") (class "Default")
      (node (ref "R3") (pin "1") (pinfunction "1_1") (pintype "passive"))
      (node (ref "U$2") (pin "LOWER_RIGHT") (pinfunction "SOURCE_LOWER_RIGHT") (pintype "bidirectional"))
      (node (ref "U$6") (pin "RIGHT") (pinfunction "EMITTER_RIGHT") (pintype "bidirectional"))
    )
    (net (code "117") (name "Net-(U$4-OUT)") (class "Default")
      (node (ref "R1") (pin "1") (pinfunction "1_1") (pintype "passive"))
      (node (ref "U$4") (pin "5") (pinfunction "OUT_5") (pintype "output"))
    )
    (net (code "118") (name "Net-(U$5-LED+)") (class "Default")
      (node (ref "R26") (pin "2") (pinfunction "2_2") (pintype "passive"))
      (node (ref "U$5") (pin "1") (pinfunction "LED+_1") (pintype "bidirectional"))
    )
    (net (code "119") (name "Net-(U$5-S1)") (class "Default")
      (node (ref "R16") (pin "1") (pinfunction "1_1") (pintype "passive"))
      (node (ref "R23") (pin "2") (pinfunction "2_2") (pintype "passive"))
      (node (ref "U$5") (pin "4") (pinfunction "S1_4") (pintype "bidirectional"))
    )
    (net (code "120") (name "Net-(U$6-BASE)") (class "Default")
      (node (ref "R13") (pin "1") (pinfunction "1_1") (pintype "passive"))
      (node (ref "R16") (pin "2") (pinfunction "2_2") (pintype "passive"))
      (node (ref "R3") (pin "2") (pinfunction "2_2") (pintype "passive"))
      (node (ref "U$6") (pin "CENTER") (pinfunction "BASE_CENTER") (pintype "bidirectional"))
    )
    (net (code "121") (name "Net-(U$15-CTS)") (class "Default")
      (node (ref "R30") (pin "2") (pinfunction "2_2") (pintype "passive"))
      (node (ref "U$15") (pin "12") (pinfunction "CTS_12") (pintype "output"))
    )
    (net (code "122") (name "Net-(U$15-RTS)") (class "Default")
      (node (ref "R28") (pin "2") (pinfunction "2_2") (pintype "passive"))
      (node (ref "U$15") (pin "16") (pinfunction "RTS_16") (pintype "input"))
    )
    (net (code "123") (name "Net-(U$16-CP)") (class "Default")
      (node (ref "U$16") (pin "11") (pinfunction "CP_11") (pintype "bidirectional"))
      (node (ref "U$20") (pin "1") (pinfunction "G_1") (pintype "bidirectional"))
    )
    (net (code "124") (name "Net-(U$16-CS)") (class "Default")
      (node (ref "R36") (pin "2") (pinfunction "2_2") (pintype "passive"))
      (node (ref "R61") (pin "2") (pinfunction "2_2") (pintype "passive"))
      (node (ref "U$16") (pin "8") (pinfunction "CS_8") (pintype "bidirectional"))
    )
    (net (code "125") (name "Net-(U$16-ENA{slash}DIAGA)") (class "Default")
      (node (ref "R39") (pin "2") (pinfunction "2_2") (pintype "passive"))
      (node (ref "U$16") (pin "5") (pinfunction "ENA/DIAGA_5") (pintype "bidirectional"))
    )
    (net (code "126") (name "Net-(U$16-ENB{slash}DIAGB)") (class "Default")
      (node (ref "R40") (pin "2") (pinfunction "2_2") (pintype "passive"))
      (node (ref "U$16") (pin "9") (pinfunction "ENB/DIAGB_9") (pintype "bidirectional"))
    )
    (net (code "127") (name "Net-(U$16-INA)") (class "Default")
      (node (ref "R63") (pin "1") (pinfunction "1_1") (pintype "passive"))
      (node (ref "U$16") (pin "4") (pinfunction "INA_4") (pintype "bidirectional"))
    )
    (net (code "128") (name "Net-(U$16-INB)") (class "Default")
      (node (ref "R62") (pin "1") (pinfunction "1_1") (pintype "passive"))
      (node (ref "U$16") (pin "10") (pinfunction "INB_10") (pintype "bidirectional"))
    )
    (net (code "129") (name "Net-(U$16-PWM)") (class "Default")
      (node (ref "R35") (pin "2") (pinfunction "2_2") (pintype "passive"))
      (node (ref "U$16") (pin "7") (pinfunction "PWM_7") (pintype "bidirectional"))
    )
    (net (code "130") (name "Net-(U$18-IN+)") (class "Default")
      (node (ref "R8") (pin "2") (pinfunction "2_2") (pintype "passive"))
      (node (ref "U$18") (pin "2") (pinfunction "IN+_2") (pintype "bidirectional"))
    )
    (net (code "131") (name "Net-(U$18-IN-)") (class "Default")
      (node (ref "R37") (pin "2") (pinfunction "2_2") (pintype "passive"))
      (node (ref "U$18") (pin "3") (pinfunction "IN-_3") (pintype "bidirectional"))
    )
    (net (code "132") (name "Net-(U$20-S)") (class "Default")
      (node (ref "C17") (pin "1") (pinfunction "1_1") (pintype "passive"))
      (node (ref "C24") (pin "1") (pinfunction "1_1") (pintype "passive"))
      (node (ref "U$16") (pin "13") (pinfunction "VCC_13") (pintype "bidirectional"))
      (node (ref "U$16") (pin "14") (pinfunction "VCC_14") (pintype "bidirectional"))
      (node (ref "U$16") (pin "2") (pinfunction "VCC_2") (pintype "bidirectional"))
      (node (ref "U$16") (pin "23") (pinfunction "VCC_23") (pintype "bidirectional"))
      (node (ref "U$16") (pin "3") (pinfunction "VCC_3") (pintype "bidirectional"))
      (node (ref "U$16") (pin "VCC") (pinfunction "VCC_VCC") (pintype "bidirectional"))
      (node (ref "U$16") (pin "VCC@1") (pinfunction "VCC_VCC@1") (pintype "bidirectional"))
      (node (ref "U$20") (pin "3") (pinfunction "S_3") (pintype "bidirectional"))
    )
    (net (code "133") (name "Net-(U$23-CP)") (class "Default")
      (node (ref "U$23") (pin "11") (pinfunction "CP_11") (pintype "bidirectional"))
      (node (ref "U$24") (pin "1") (pinfunction "G_1") (pintype "bidirectional"))
    )
    (net (code "134") (name "Net-(U$23-CS)") (class "Default")
      (node (ref "R65") (pin "2") (pinfunction "2_2") (pintype "passive"))
      (node (ref "R72") (pin "2") (pinfunction "2_2") (pintype "passive"))
      (node (ref "U$23") (pin "8") (pinfunction "CS_8") (pintype "bidirectional"))
    )
    (net (code "135") (name "Net-(U$23-ENA{slash}DIAGA)") (class "Default")
      (node (ref "R67") (pin "2") (pinfunction "2_2") (pintype "passive"))
      (node (ref "U$23") (pin "5") (pinfunction "ENA/DIAGA_5") (pintype "bidirectional"))
    )
    (net (code "136") (name "Net-(U$23-ENB{slash}DIAGB)") (class "Default")
      (node (ref "R68") (pin "2") (pinfunction "2_2") (pintype "passive"))
      (node (ref "U$23") (pin "9") (pinfunction "ENB/DIAGB_9") (pintype "bidirectional"))
    )
    (net (code "137") (name "Net-(U$23-INA)") (class "Default")
      (node (ref "R74") (pin "1") (pinfunction "1_1") (pintype "passive"))
      (node (ref "U$23") (pin "4") (pinfunction "INA_4") (pintype "bidirectional"))
    )
    (net (code "138") (name "Net-(U$23-INB)") (class "Default")
      (node (ref "R73") (pin "1") (pinfunction "1_1") (pintype "passive"))
      (node (ref "U$23") (pin "10") (pinfunction "INB_10") (pintype "bidirectional"))
    )
    (net (code "139") (name "Net-(U$23-PWM)") (class "Default")
      (node (ref "R64") (pin "2") (pinfunction "2_2") (pintype "passive"))
      (node (ref "U$23") (pin "7") (pinfunction "PWM_7") (pintype "bidirectional"))
    )
    (net (code "140") (name "Net-(U$24-S)") (class "Default")
      (node (ref "C26") (pin "1") (pinfunction "1_1") (pintype "passive"))
      (node (ref "C27") (pin "1") (pinfunction "1_1") (pintype "passive"))
      (node (ref "U$23") (pin "13") (pinfunction "VCC_13") (pintype "bidirectional"))
      (node (ref "U$23") (pin "14") (pinfunction "VCC_14") (pintype "bidirectional"))
      (node (ref "U$23") (pin "2") (pinfunction "VCC_2") (pintype "bidirectional"))
      (node (ref "U$23") (pin "23") (pinfunction "VCC_23") (pintype "bidirectional"))
      (node (ref "U$23") (pin "3") (pinfunction "VCC_3") (pintype "bidirectional"))
      (node (ref "U$23") (pin "VCC") (pinfunction "VCC_VCC") (pintype "bidirectional"))
      (node (ref "U$23") (pin "VCC@1") (pinfunction "VCC_VCC@1") (pintype "bidirectional"))
      (node (ref "U$24") (pin "3") (pinfunction "S_3") (pintype "bidirectional"))
    )
    (net (code "141") (name "Net-(U$25-CP)") (class "Default")
      (node (ref "U$25") (pin "11") (pinfunction "CP_11") (pintype "bidirectional"))
      (node (ref "U$26") (pin "1") (pinfunction "G_1") (pintype "bidirectional"))
    )
    (net (code "142") (name "Net-(U$25-CS)") (class "Default")
      (node (ref "R76") (pin "2") (pinfunction "2_2") (pintype "passive"))
      (node (ref "R83") (pin "2") (pinfunction "2_2") (pintype "passive"))
      (node (ref "U$25") (pin "8") (pinfunction "CS_8") (pintype "bidirectional"))
    )
    (net (code "143") (name "Net-(U$25-ENA{slash}DIAGA)") (class "Default")
      (node (ref "R78") (pin "2") (pinfunction "2_2") (pintype "passive"))
      (node (ref "U$25") (pin "5") (pinfunction "ENA/DIAGA_5") (pintype "bidirectional"))
    )
    (net (code "144") (name "Net-(U$25-ENB{slash}DIAGB)") (class "Default")
      (node (ref "R79") (pin "2") (pinfunction "2_2") (pintype "passive"))
      (node (ref "U$25") (pin "9") (pinfunction "ENB/DIAGB_9") (pintype "bidirectional"))
    )
    (net (code "145") (name "Net-(U$25-INA)") (class "Default")
      (node (ref "R85") (pin "1") (pinfunction "1_1") (pintype "passive"))
      (node (ref "U$25") (pin "4") (pinfunction "INA_4") (pintype "bidirectional"))
    )
    (net (code "146") (name "Net-(U$25-INB)") (class "Default")
      (node (ref "R84") (pin "1") (pinfunction "1_1") (pintype "passive"))
      (node (ref "U$25") (pin "10") (pinfunction "INB_10") (pintype "bidirectional"))
    )
    (net (code "147") (name "Net-(U$25-PWM)") (class "Default")
      (node (ref "R75") (pin "2") (pinfunction "2_2") (pintype "passive"))
      (node (ref "U$25") (pin "7") (pinfunction "PWM_7") (pintype "bidirectional"))
    )
    (net (code "148") (name "Net-(U$26-S)") (class "Default")
      (node (ref "C30") (pin "1") (pinfunction "1_1") (pintype "passive"))
      (node (ref "C31") (pin "1") (pinfunction "1_1") (pintype "passive"))
      (node (ref "U$25") (pin "13") (pinfunction "VCC_13") (pintype "bidirectional"))
      (node (ref "U$25") (pin "14") (pinfunction "VCC_14") (pintype "bidirectional"))
      (node (ref "U$25") (pin "2") (pinfunction "VCC_2") (pintype "bidirectional"))
      (node (ref "U$25") (pin "23") (pinfunction "VCC_23") (pintype "bidirectional"))
      (node (ref "U$25") (pin "3") (pinfunction "VCC_3") (pintype "bidirectional"))
      (node (ref "U$25") (pin "VCC") (pinfunction "VCC_VCC") (pintype "bidirectional"))
      (node (ref "U$25") (pin "VCC@1") (pinfunction "VCC_VCC@1") (pintype "bidirectional"))
      (node (ref "U$26") (pin "3") (pinfunction "S_3") (pintype "bidirectional"))
    )
    (net (code "149") (name "Net-(U$27-CP)") (class "Default")
      (node (ref "U$27") (pin "11") (pinfunction "CP_11") (pintype "bidirectional"))
      (node (ref "U$28") (pin "1") (pinfunction "G_1") (pintype "bidirectional"))
    )
    (net (code "150") (name "Net-(U$27-CS)") (class "Default")
      (node (ref "R87") (pin "2") (pinfunction "2_2") (pintype "passive"))
      (node (ref "R94") (pin "2") (pinfunction "2_2") (pintype "passive"))
      (node (ref "U$27") (pin "8") (pinfunction "CS_8") (pintype "bidirectional"))
    )
    (net (code "151") (name "Net-(U$27-ENA{slash}DIAGA)") (class "Default")
      (node (ref "R89") (pin "2") (pinfunction "2_2") (pintype "passive"))
      (node (ref "U$27") (pin "5") (pinfunction "ENA/DIAGA_5") (pintype "bidirectional"))
    )
    (net (code "152") (name "Net-(U$27-ENB{slash}DIAGB)") (class "Default")
      (node (ref "R90") (pin "2") (pinfunction "2_2") (pintype "passive"))
      (node (ref "U$27") (pin "9") (pinfunction "ENB/DIAGB_9") (pintype "bidirectional"))
    )
    (net (code "153") (name "Net-(U$27-INA)") (class "Default")
      (node (ref "R96") (pin "1") (pinfunction "1_1") (pintype "passive"))
      (node (ref "U$27") (pin "4") (pinfunction "INA_4") (pintype "bidirectional"))
    )
    (net (code "154") (name "Net-(U$27-INB)") (class "Default")
      (node (ref "R95") (pin "1") (pinfunction "1_1") (pintype "passive"))
      (node (ref "U$27") (pin "10") (pinfunction "INB_10") (pintype "bidirectional"))
    )
    (net (code "155") (name "Net-(U$27-PWM)") (class "Default")
      (node (ref "R86") (pin "2") (pinfunction "2_2") (pintype "passive"))
      (node (ref "U$27") (pin "7") (pinfunction "PWM_7") (pintype "bidirectional"))
    )
    (net (code "156") (name "Net-(U$28-S)") (class "Default")
      (node (ref "C43") (pin "1") (pinfunction "1_1") (pintype "passive"))
      (node (ref "C44") (pin "1") (pinfunction "1_1") (pintype "passive"))
      (node (ref "U$27") (pin "13") (pinfunction "VCC_13") (pintype "bidirectional"))
      (node (ref "U$27") (pin "14") (pinfunction "VCC_14") (pintype "bidirectional"))
      (node (ref "U$27") (pin "2") (pinfunction "VCC_2") (pintype "bidirectional"))
      (node (ref "U$27") (pin "23") (pinfunction "VCC_23") (pintype "bidirectional"))
      (node (ref "U$27") (pin "3") (pinfunction "VCC_3") (pintype "bidirectional"))
      (node (ref "U$27") (pin "VCC") (pinfunction "VCC_VCC") (pintype "bidirectional"))
      (node (ref "U$27") (pin "VCC@1") (pinfunction "VCC_VCC@1") (pintype "bidirectional"))
      (node (ref "U$28") (pin "3") (pinfunction "S_3") (pintype "bidirectional"))
    )
    (net (code "157") (name "unconnected-(U$14-A21{slash}DAC0-Pad21{slash}DAC0)") (class "Default")
      (node (ref "U$14") (pin "21/DAC0") (pinfunction "A21/DAC0_21/DAC0") (pintype "bidirectional"))
    )
    (net (code "158") (name "unconnected-(U$14-Pad3V3)") (class "Default")
      (node (ref "U$14") (pin "3V3") (pinfunction "3V3_3V3") (pintype "bidirectional"))
    )
    (net (code "159") (name "unconnected-(U$14-Pad3V3_2)") (class "Default")
      (node (ref "U$14") (pin "3V3_2") (pinfunction "3V3_2_3V3_2") (pintype "bidirectional"))
    )
    (net (code "160") (name "unconnected-(U$14-Pad3V3_LO)") (class "Default")
      (node (ref "U$14") (pin "3V3_LO") (pinfunction "3V3_LO_3V3_LO") (pintype "bidirectional"))
    )
    (net (code "161") (name "unconnected-(U$14-Pad8)") (class "Default")
      (node (ref "U$14") (pin "8") (pinfunction "8_8") (pintype "bidirectional"))
    )
    (net (code "162") (name "unconnected-(U$14-Pad11{slash}MOSI)") (class "Default")
      (node (ref "U$14") (pin "11/MOSI") (pinfunction "11/MOSI_11/MOSI") (pintype "bidirectional"))
    )
    (net (code "163") (name "unconnected-(U$14-Pad12{slash}MISO)") (class "Default")
      (node (ref "U$14") (pin "12/MISO") (pinfunction "12/MISO_12/MISO") (pintype "bidirectional"))
    )
    (net (code "164") (name "unconnected-(U$14-Pad13{slash}SCK)") (class "Default")
      (node (ref "U$14") (pin "13/SCK") (pinfunction "13/SCK_13/SCK") (pintype "bidirectional"))
    )
    (net (code "165") (name "unconnected-(U$14-Pad20{slash}A6)") (class "Default")
      (node (ref "U$14") (pin "20/A6") (pinfunction "20/A6_20/A6") (pintype "bidirectional"))
    )
    (net (code "166") (name "unconnected-(U$14-Pad30)") (class "Default")
      (node (ref "U$14") (pin "30") (pinfunction "30_30") (pintype "bidirectional"))
    )
    (net (code "167") (name "unconnected-(U$14-Pad38{slash}A19)") (class "Default")
      (node (ref "U$14") (pin "38/A19") (pinfunction "38/A19_38/A19") (pintype "bidirectional"))
    )
    (net (code "168") (name "unconnected-(U$14-PadA10)") (class "Default")
      (node (ref "U$14") (pin "A10") (pinfunction "A10_A10") (pintype "bidirectional"))
    )
    (net (code "169") (name "unconnected-(U$14-PadA11)") (class "Default")
      (node (ref "U$14") (pin "A11") (pinfunction "A11_A11") (pintype "bidirectional"))
    )
    (net (code "170") (name "unconnected-(U$14-PadAREF)") (class "Default")
      (node (ref "U$14") (pin "AREF") (pinfunction "AREF_AREF") (pintype "bidirectional"))
    )
    (net (code "171") (name "unconnected-(U$14-PadGND3)") (class "Default")
      (node (ref "U$14") (pin "GND3") (pinfunction "GND3_GND3") (pintype "bidirectional"))
    )
    (net (code "172") (name "unconnected-(U$14-PadPROG)") (class "Default")
      (node (ref "U$14") (pin "PROG") (pinfunction "PROG_PROG") (pintype "bidirectional"))
    )
    (net (code "173") (name "unconnected-(U$14-PadRESET)") (class "Default")
      (node (ref "U$14") (pin "RESET") (pinfunction "RESET_RESET") (pintype "bidirectional"))
    )
    (net (code "174") (name "unconnected-(U$14-PadU5V)") (class "Default")
      (node (ref "U$14") (pin "U5V") (pinfunction "U5V_U5V") (pintype "bidirectional"))
    )
    (net (code "175") (name "unconnected-(U$14-PadUD+)") (class "Default")
      (node (ref "U$14") (pin "UD+") (pinfunction "UD+_UD+") (pintype "bidirectional"))
    )
    (net (code "176") (name "unconnected-(U$14-PadUD-)") (class "Default")
      (node (ref "U$14") (pin "UD-") (pinfunction "UD-_UD-") (pintype "bidirectional"))
    )
    (net (code "177") (name "unconnected-(U$14-PadUGND1)") (class "Default")
      (node (ref "U$14") (pin "UGND1") (pinfunction "UGND1_UGND1") (pintype "bidirectional"))
    )
    (net (code "178") (name "unconnected-(U$14-PadUGND2)") (class "Default")
      (node (ref "U$14") (pin "UGND2") (pinfunction "UGND2_UGND2") (pintype "bidirectional"))
    )
    (net (code "179") (name "unconnected-(U$14-PadVBAT)") (class "Default")
      (node (ref "U$14") (pin "VBAT") (pinfunction "VBAT_VBAT") (pintype "bidirectional"))
    )
    (net (code "180") (name "unconnected-(U$14-PadVUSB)") (class "Default")
      (node (ref "U$14") (pin "VUSB") (pinfunction "VUSB_VUSB") (pintype "bidirectional"))
    )
    (net (code "181") (name "unconnected-(U$15-DIO0-Pad20)") (class "Default")
      (node (ref "U$15") (pin "20") (pinfunction "DIO0_20") (pintype "bidirectional"))
    )
    (net (code "182") (name "unconnected-(U$15-DIO1-Pad19)") (class "Default")
      (node (ref "U$15") (pin "19") (pinfunction "DIO1_19") (pintype "bidirectional"))
    )
    (net (code "183") (name "unconnected-(U$15-DIO2-Pad18)") (class "Default")
      (node (ref "U$15") (pin "18") (pinfunction "DIO2_18") (pintype "bidirectional"))
    )
    (net (code "184") (name "unconnected-(U$15-DIO3-Pad17)") (class "Default")
      (node (ref "U$15") (pin "17") (pinfunction "DIO3_17") (pintype "bidirectional"))
    )
    (net (code "185") (name "unconnected-(U$15-DIO4-Pad11)") (class "Default")
      (node (ref "U$15") (pin "11") (pinfunction "DIO4_11") (pintype "bidirectional"))
    )
    (net (code "186") (name "unconnected-(U$15-DIO5-Pad15)") (class "Default")
      (node (ref "U$15") (pin "15") (pinfunction "DIO5_15") (pintype "bidirectional"))
    )
    (net (code "187") (name "unconnected-(U$15-DIO9-Pad13)") (class "Default")
      (node (ref "U$15") (pin "13") (pinfunction "DIO9_13") (pintype "bidirectional"))
    )
    (net (code "188") (name "unconnected-(U$15-DIO11-Pad7)") (class "Default")
      (node (ref "U$15") (pin "7") (pinfunction "DIO11_7") (pintype "bidirectional"))
    )
    (net (code "189") (name "unconnected-(U$15-DIO12-Pad4)") (class "Default")
      (node (ref "U$15") (pin "4") (pinfunction "DIO12_4") (pintype "bidirectional"))
    )
    (net (code "190") (name "unconnected-(U$15-DTR-Pad9)") (class "Default")
      (node (ref "U$15") (pin "9") (pinfunction "DTR_9") (pintype "bidirectional"))
    )
    (net (code "191") (name "unconnected-(U$15-RES-Pad8)") (class "Default")
      (node (ref "U$15") (pin "8") (pinfunction "RES_8") (pintype "bidirectional"))
    )
    (net (code "192") (name "unconnected-(U$15-RES-Pad14)") (class "Default")
      (node (ref "U$15") (pin "14") (pinfunction "RES_14") (pintype "bidirectional"))
    )
    (net (code "193") (name "unconnected-(U$15-RSSI-Pad6)") (class "Default")
      (node (ref "U$15") (pin "6") (pinfunction "RSSI_6") (pintype "bidirectional"))
    )
    (net (code "194") (name "unconnected-(U$16-CS_DIS-Pad6)") (class "Default")
      (node (ref "U$16") (pin "6") (pinfunction "CS_DIS_6") (pintype "bidirectional"))
    )
    (net (code "195") (name "unconnected-(U$17-GPA0-Pad21)") (class "Default")
      (node (ref "U$17") (pin "21") (pinfunction "GPA0_21") (pintype "bidirectional"))
    )
    (net (code "196") (name "unconnected-(U$17-GPA1-Pad22)") (class "Default")
      (node (ref "U$17") (pin "22") (pinfunction "GPA1_22") (pintype "bidirectional"))
    )
    (net (code "197") (name "unconnected-(U$17-GPA2-Pad23)") (class "Default")
      (node (ref "U$17") (pin "23") (pinfunction "GPA2_23") (pintype "bidirectional"))
    )
    (net (code "198") (name "unconnected-(U$17-GPA3-Pad24)") (class "Default")
      (node (ref "U$17") (pin "24") (pinfunction "GPA3_24") (pintype "bidirectional"))
    )
    (net (code "199") (name "unconnected-(U$17-GPB4-Pad5)") (class "Default")
      (node (ref "U$17") (pin "5") (pinfunction "GPB4_5") (pintype "bidirectional"))
    )
    (net (code "200") (name "unconnected-(U$17-GPB5-Pad6)") (class "Default")
      (node (ref "U$17") (pin "6") (pinfunction "GPB5_6") (pintype "bidirectional"))
    )
    (net (code "201") (name "unconnected-(U$17-GPB6-Pad7)") (class "Default")
      (node (ref "U$17") (pin "7") (pinfunction "GPB6_7") (pintype "bidirectional"))
    )
    (net (code "202") (name "unconnected-(U$17-GPB7-Pad8)") (class "Default")
      (node (ref "U$17") (pin "8") (pinfunction "GPB7_8") (pintype "bidirectional"))
    )
    (net (code "203") (name "unconnected-(U$17-INTB-Pad19)") (class "Default")
      (node (ref "U$17") (pin "19") (pinfunction "INTB_19") (pintype "bidirectional"))
    )
    (net (code "204") (name "unconnected-(U$17-NC0-Pad11)") (class "Default")
      (node (ref "U$17") (pin "11") (pinfunction "NC0_11") (pintype "bidirectional"))
    )
    (net (code "205") (name "unconnected-(U$17-NC1-Pad14)") (class "Default")
      (node (ref "U$17") (pin "14") (pinfunction "NC1_14") (pintype "bidirectional"))
    )
    (net (code "206") (name "unconnected-(U$18-BAL-Pad5)") (class "Default")
      (node (ref "U$18") (pin "5") (pinfunction "BAL_5") (pintype "bidirectional"))
    )
    (net (code "207") (name "unconnected-(U$18-BAL{slash}STRB-Pad6)") (class "Default")
      (node (ref "U$18") (pin "6") (pinfunction "BAL/STRB_6") (pintype "bidirectional"))
    )
    (net (code "208") (name "unconnected-(U$21-GPA0-Pad21)") (class "Default")
      (node (ref "U$21") (pin "21") (pinfunction "GPA0_21") (pintype "bidirectional"))
    )
    (net (code "209") (name "unconnected-(U$21-GPA1-Pad22)") (class "Default")
      (node (ref "U$21") (pin "22") (pinfunction "GPA1_22") (pintype "bidirectional"))
    )
    (net (code "210") (name "unconnected-(U$21-GPA2-Pad23)") (class "Default")
      (node (ref "U$21") (pin "23") (pinfunction "GPA2_23") (pintype "bidirectional"))
    )
    (net (code "211") (name "unconnected-(U$21-GPA3-Pad24)") (class "Default")
      (node (ref "U$21") (pin "24") (pinfunction "GPA3_24") (pintype "bidirectional"))
    )
    (net (code "212") (name "unconnected-(U$21-GPB4-Pad5)") (class "Default")
      (node (ref "U$21") (pin "5") (pinfunction "GPB4_5") (pintype "bidirectional"))
    )
    (net (code "213") (name "unconnected-(U$21-GPB5-Pad6)") (class "Default")
      (node (ref "U$21") (pin "6") (pinfunction "GPB5_6") (pintype "bidirectional"))
    )
    (net (code "214") (name "unconnected-(U$21-GPB6-Pad7)") (class "Default")
      (node (ref "U$21") (pin "7") (pinfunction "GPB6_7") (pintype "bidirectional"))
    )
    (net (code "215") (name "unconnected-(U$21-GPB7-Pad8)") (class "Default")
      (node (ref "U$21") (pin "8") (pinfunction "GPB7_8") (pintype "bidirectional"))
    )
    (net (code "216") (name "unconnected-(U$21-INTB-Pad19)") (class "Default")
      (node (ref "U$21") (pin "19") (pinfunction "INTB_19") (pintype "bidirectional"))
    )
    (net (code "217") (name "unconnected-(U$21-NC0-Pad11)") (class "Default")
      (node (ref "U$21") (pin "11") (pinfunction "NC0_11") (pintype "bidirectional"))
    )
    (net (code "218") (name "unconnected-(U$21-NC1-Pad14)") (class "Default")
      (node (ref "U$21") (pin "14") (pinfunction "NC1_14") (pintype "bidirectional"))
    )
    (net (code "219") (name "unconnected-(U$23-CS_DIS-Pad6)") (class "Default")
      (node (ref "U$23") (pin "6") (pinfunction "CS_DIS_6") (pintype "bidirectional"))
    )
    (net (code "220") (name "unconnected-(U$25-CS_DIS-Pad6)") (class "Default")
      (node (ref "U$25") (pin "6") (pinfunction "CS_DIS_6") (pintype "bidirectional"))
    )
    (net (code "221") (name "unconnected-(U$27-CS_DIS-Pad6)") (class "Default")
      (node (ref "U$27") (pin "6") (pinfunction "CS_DIS_6") (pintype "bidirectional"))
    )
  )
)
